# COM-TC.net
KiCad netlist of a schematic drawn in EAGLE
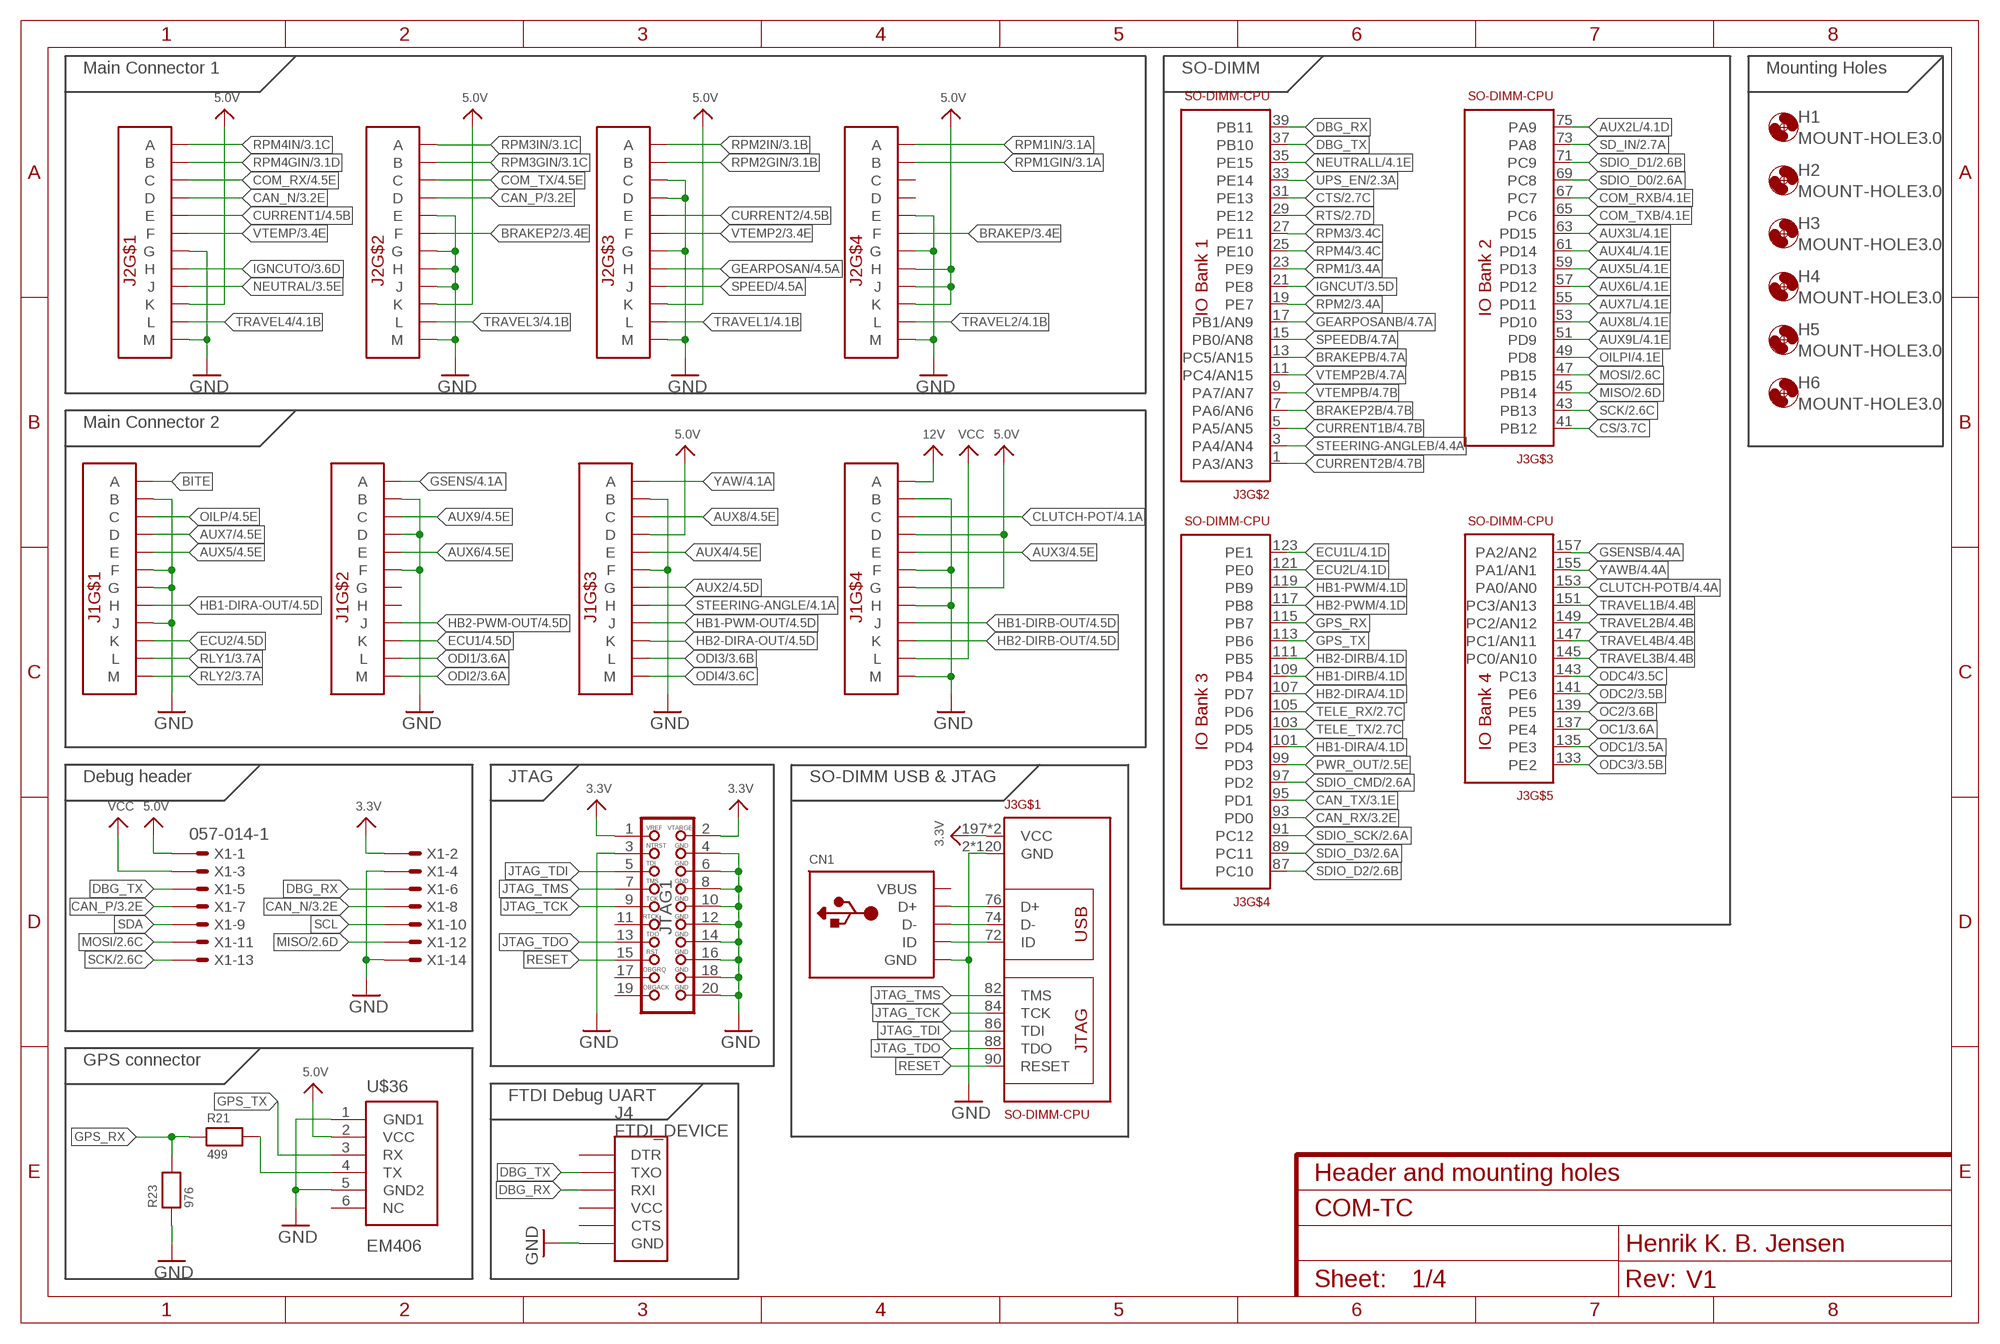
[diagram p0: schematic, sheet 1]
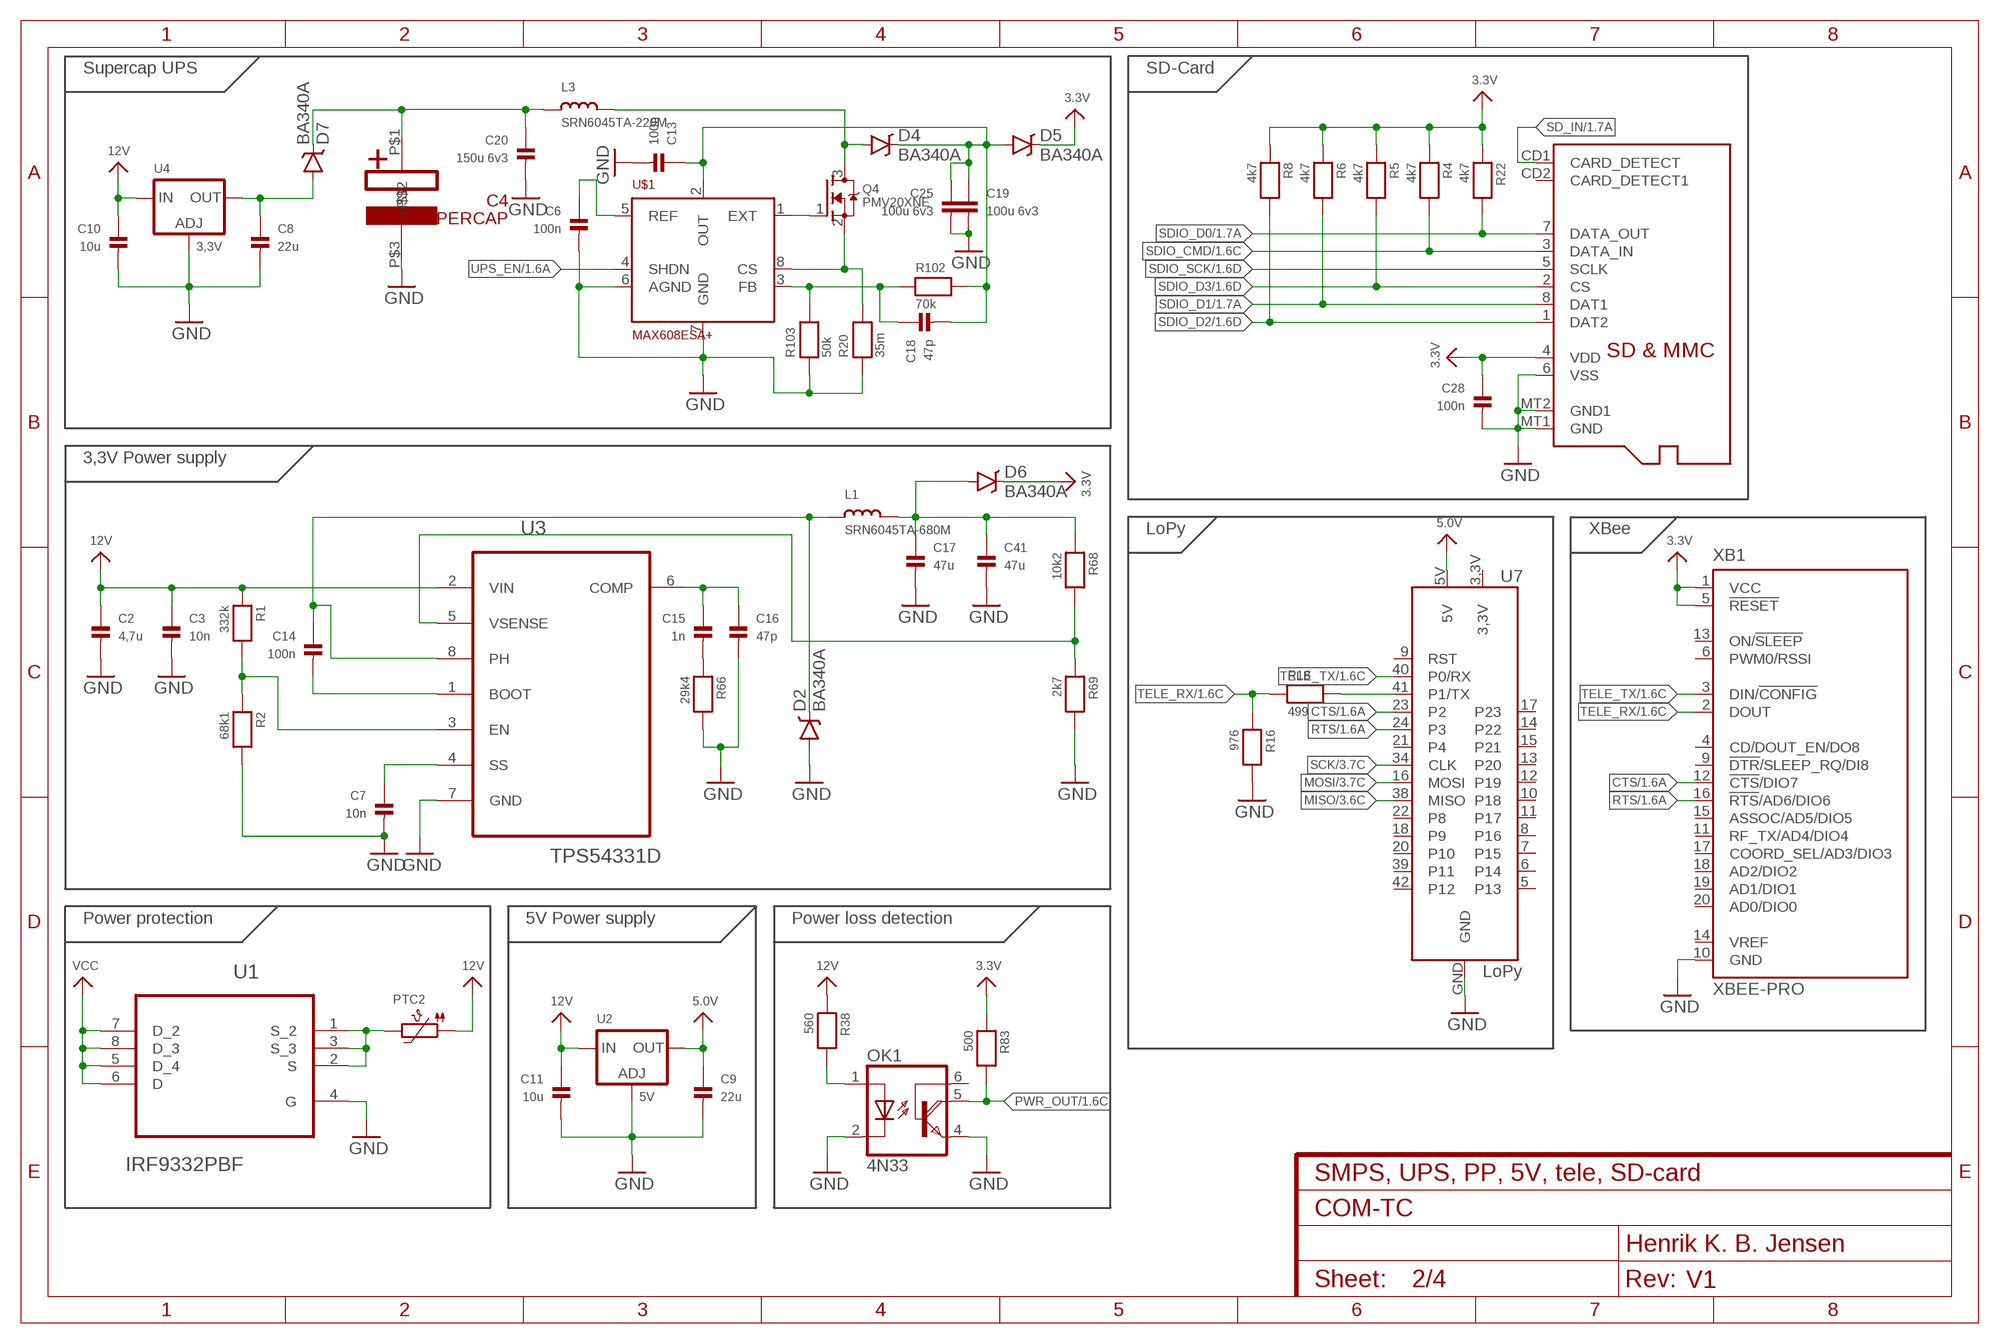
[diagram p1: schematic, sheet 2]
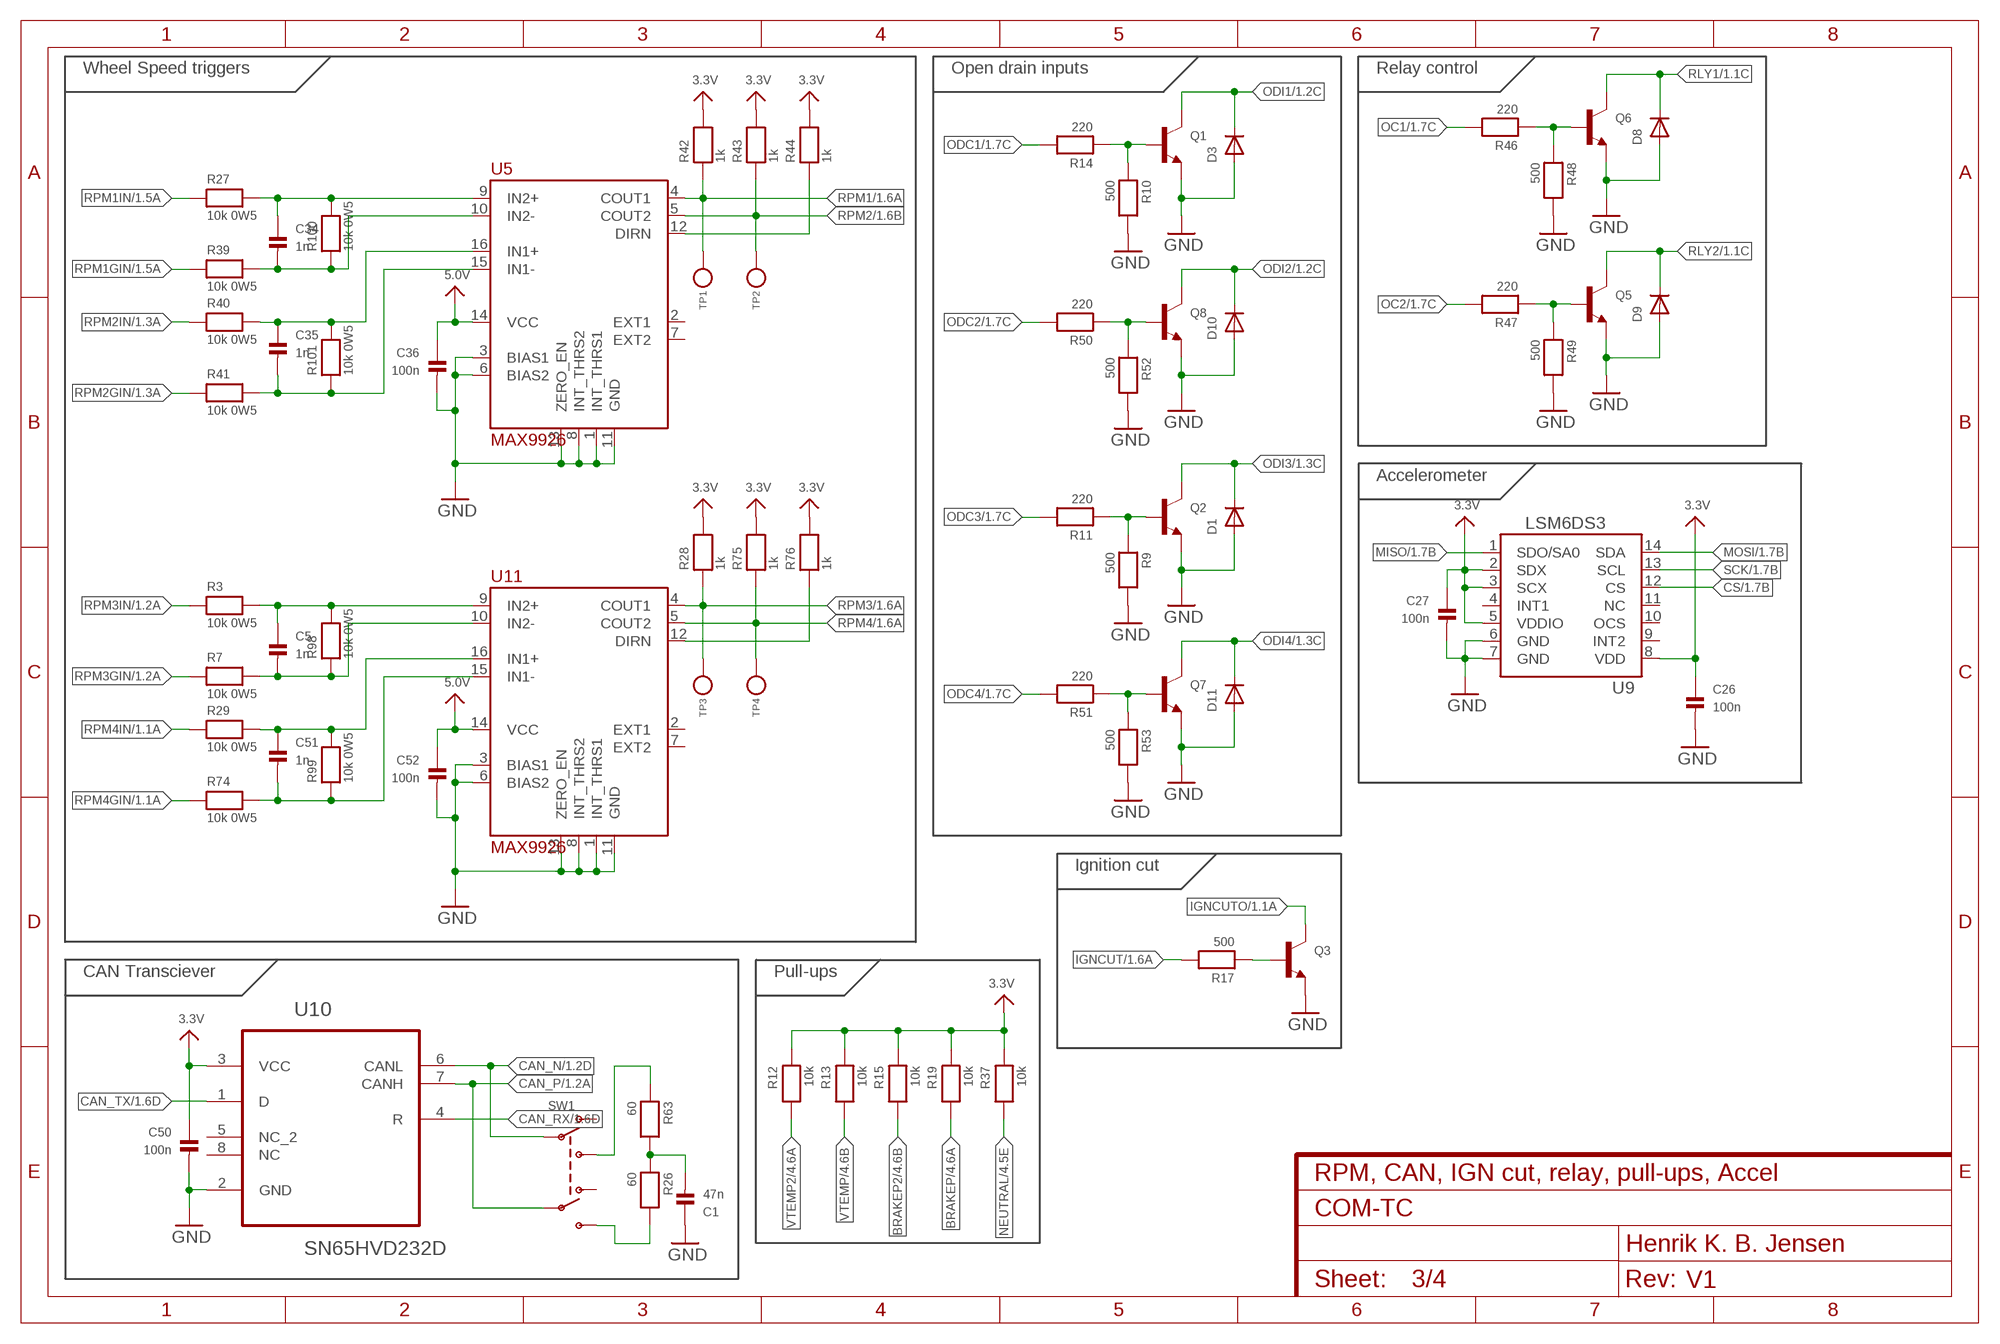
[diagram p2: schematic, sheet 3]
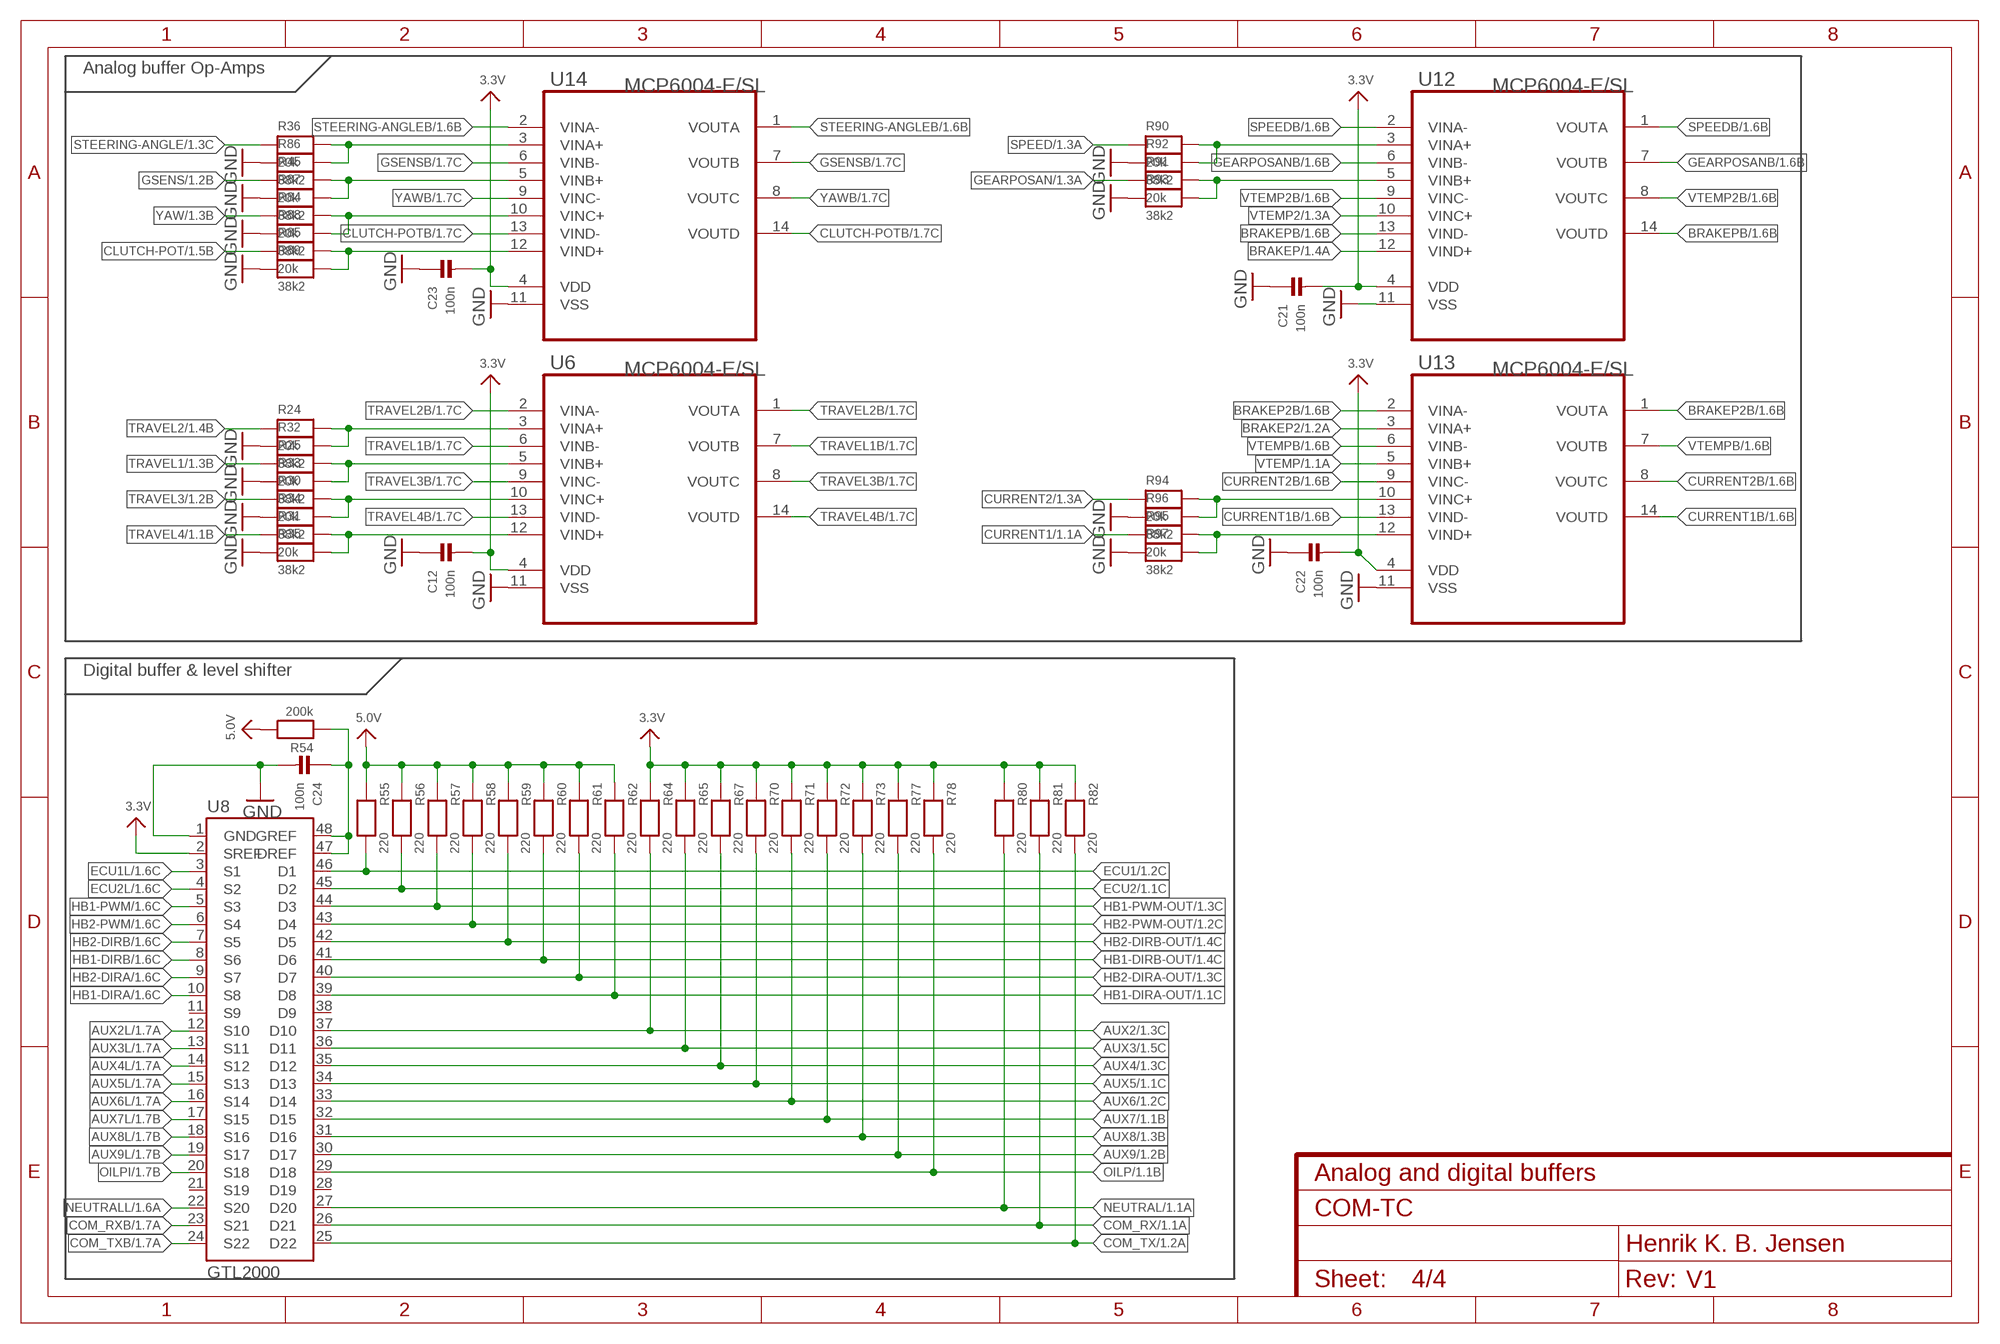
[diagram p3: schematic, sheet 4]

(export (version "E")
  (design (tool "Eeschema 10.0.6"))
  (components
    (comp (ref "C2")
      (value "4,7u")
      (footprint "eagle-import:_0805")
      (libsource (lib "eagle-import") (part "CAP_CERAMIC_0805"))
    )
    (comp (ref "C3")
      (value "10n")
      (footprint "eagle-import:_0603")
      (libsource (lib "eagle-import") (part "CAP_CERAMIC_0603"))
    )
    (comp (ref "C4")
      (value "SUPERCAP")
      (footprint "eagle-import:SUPERCAP")
      (libsource (lib "eagle-import") (part "SUPERCAP"))
    )
    (comp (ref "C6")
      (value "100n")
      (footprint "eagle-import:_0603")
      (libsource (lib "eagle-import") (part "CAP_CERAMIC_0603"))
    )
    (comp (ref "C7")
      (value "10n")
      (footprint "eagle-import:_0603")
      (libsource (lib "eagle-import") (part "CAP_CERAMIC_0603"))
    )
    (comp (ref "C8")
      (value "22u")
      (footprint "eagle-import:_0805")
      (libsource (lib "eagle-import") (part "CAP_CERAMIC_0805"))
    )
    (comp (ref "C9")
      (value "22u")
      (footprint "eagle-import:_0805")
      (libsource (lib "eagle-import") (part "CAP_CERAMIC_0805"))
    )
    (comp (ref "C10")
      (value "10u")
      (footprint "eagle-import:_0805")
      (libsource (lib "eagle-import") (part "CAP_CERAMIC_0805"))
    )
    (comp (ref "C11")
      (value "10u")
      (footprint "eagle-import:_0805")
      (libsource (lib "eagle-import") (part "CAP_CERAMIC_0805"))
    )
    (comp (ref "C13")
      (value "100n")
      (footprint "eagle-import:_0603")
      (libsource (lib "eagle-import") (part "CAP_CERAMIC_0603"))
    )
    (comp (ref "C14")
      (value "100n")
      (footprint "eagle-import:_0603")
      (libsource (lib "eagle-import") (part "CAP_CERAMIC_0603"))
    )
    (comp (ref "C15")
      (value "1n")
      (footprint "eagle-import:_0603")
      (libsource (lib "eagle-import") (part "CAP_CERAMIC_0603"))
    )
    (comp (ref "C16")
      (value "47p")
      (footprint "eagle-import:_0603")
      (libsource (lib "eagle-import") (part "CAP_CERAMIC_0603"))
    )
    (comp (ref "C17")
      (value "47u")
      (footprint "eagle-import:_0805")
      (libsource (lib "eagle-import") (part "CAP_CERAMIC_0805"))
    )
    (comp (ref "C18")
      (value "47p")
      (footprint "eagle-import:_0603")
      (libsource (lib "eagle-import") (part "CAP_CERAMIC_0603"))
    )
    (comp (ref "C19")
      (value "100u 6v3")
      (footprint "eagle-import:1206")
      (libsource (lib "eagle-import") (part "CAP_CERAMIC1206"))
    )
    (comp (ref "C20")
      (value "150u 6v3")
      (footprint "eagle-import:1206")
      (libsource (lib "eagle-import") (part "CAP_CERAMIC1206"))
    )
    (comp (ref "C25")
      (value "100u 6v3")
      (footprint "eagle-import:1206")
      (libsource (lib "eagle-import") (part "CAP_CERAMIC1206"))
    )
    (comp (ref "C28")
      (value "100n")
      (footprint "eagle-import:_0603")
      (libsource (lib "eagle-import") (part "CAP_CERAMIC_0603"))
    )
    (comp (ref "C41")
      (value "47u")
      (footprint "eagle-import:_0805")
      (libsource (lib "eagle-import") (part "CAP_CERAMIC_0805"))
    )
    (comp (ref "D2")
      (value "BA340A")
      (footprint "eagle-import:SMA-DIODE")
      (libsource (lib "eagle-import") (part "B340A"))
    )
    (comp (ref "D4")
      (value "BA340A")
      (footprint "eagle-import:SMA-DIODE")
      (libsource (lib "eagle-import") (part "B340A"))
    )
    (comp (ref "D5")
      (value "BA340A")
      (footprint "eagle-import:SMA-DIODE")
      (libsource (lib "eagle-import") (part "B340A"))
    )
    (comp (ref "D6")
      (value "BA340A")
      (footprint "eagle-import:SMA-DIODE")
      (libsource (lib "eagle-import") (part "B340A"))
    )
    (comp (ref "D7")
      (value "BA340A")
      (footprint "eagle-import:SMA-DIODE")
      (libsource (lib "eagle-import") (part "B340A"))
    )
    (comp (ref "L1")
      (value "SRN6045TA-680M")
      (footprint "eagle-import:INDUCTOR_6X6MM_TDK_VLC6045")
      (libsource (lib "eagle-import") (part "INDUCTORTDK_VLC6045"))
    )
    (comp (ref "L3")
      (value "SRN6045TA-220M")
      (footprint "eagle-import:INDUCTOR_6X6MM_TDK_VLC6045")
      (libsource (lib "eagle-import") (part "INDUCTORTDK_VLC6045"))
    )
    (comp (ref "OK1")
      (value "4N33")
      (footprint "eagle-import:DIL06")
      (fields (field (name "MF") "VISHAY/TELEFUNKEN"))
      (libsource (lib "eagle-import") (part "4N33"))
    )
    (comp (ref "PTC2")
      (value "PTC1812")
      (footprint "eagle-import:PTC1812")
      (libsource (lib "eagle-import") (part "PTC1812"))
    )
    (comp (ref "Q4")
      (value "PMV20XNE")
      (footprint "eagle-import:SOT23")
      (libsource (lib "eagle-import") (part "MOSFET-NREFLOW"))
    )
    (comp (ref "R1")
      (value "332k")
      (footprint "eagle-import:_0603")
      (libsource (lib "eagle-import") (part "RESISTOR_0603"))
    )
    (comp (ref "R2")
      (value "68k1")
      (footprint "eagle-import:_0603")
      (libsource (lib "eagle-import") (part "RESISTOR_0603"))
    )
    (comp (ref "R4")
      (value "4k7")
      (footprint "eagle-import:_0603")
      (libsource (lib "eagle-import") (part "RESISTOR_0603"))
    )
    (comp (ref "R5")
      (value "4k7")
      (footprint "eagle-import:_0603")
      (libsource (lib "eagle-import") (part "RESISTOR_0603"))
    )
    (comp (ref "R6")
      (value "4k7")
      (footprint "eagle-import:_0603")
      (libsource (lib "eagle-import") (part "RESISTOR_0603"))
    )
    (comp (ref "R8")
      (value "4k7")
      (footprint "eagle-import:_0603")
      (libsource (lib "eagle-import") (part "RESISTOR_0603"))
    )
    (comp (ref "R16")
      (value "976")
      (footprint "eagle-import:_0603")
      (libsource (lib "eagle-import") (part "RESISTOR_0603"))
    )
    (comp (ref "R18")
      (value "499")
      (footprint "eagle-import:_0603")
      (libsource (lib "eagle-import") (part "RESISTOR_0603"))
    )
    (comp (ref "R20")
      (value "35m")
      (footprint "eagle-import:1206")
      (libsource (lib "eagle-import") (part "RESISTOR1206"))
    )
    (comp (ref "R22")
      (value "4k7")
      (footprint "eagle-import:_0603")
      (libsource (lib "eagle-import") (part "RESISTOR_0603"))
    )
    (comp (ref "R38")
      (value "560")
      (footprint "eagle-import:_0603")
      (libsource (lib "eagle-import") (part "RESISTOR_0603"))
    )
    (comp (ref "R66")
      (value "29k4")
      (footprint "eagle-import:_0603")
      (libsource (lib "eagle-import") (part "RESISTOR_0603"))
    )
    (comp (ref "R68")
      (value "10k2")
      (footprint "eagle-import:_0603")
      (libsource (lib "eagle-import") (part "RESISTOR_0603"))
    )
    (comp (ref "R69")
      (value "2k7")
      (footprint "eagle-import:_0603")
      (libsource (lib "eagle-import") (part "RESISTOR_0603"))
    )
    (comp (ref "R83")
      (value "500")
      (footprint "eagle-import:_0603")
      (libsource (lib "eagle-import") (part "RESISTOR_0603"))
    )
    (comp (ref "R102")
      (value "70k")
      (footprint "eagle-import:_0603")
      (libsource (lib "eagle-import") (part "RESISTOR_0603"))
    )
    (comp (ref "R103")
      (value "50k")
      (footprint "eagle-import:_0603")
      (libsource (lib "eagle-import") (part "RESISTOR_0603"))
    )
    (comp (ref "U$1")
      (value "MAX608ESA+")
      (footprint "eagle-import:SO08")
      (libsource (lib "eagle-import") (part "MAX608ESA+"))
    )
    (comp (ref "U$2")
      (value "MICROSD")
      (footprint "eagle-import:MICROSD")
      (libsource (lib "eagle-import") (part "MICROSD"))
    )
    (comp (ref "U1")
      (value "IRF9332PBF")
      (footprint "eagle-import:SOIC127P600X175-8N")
      (libsource (lib "eagle-import") (part "IRF9332PBF"))
    )
    (comp (ref "U2")
      (value "5V")
      (footprint "eagle-import:SOT223-R")
      (libsource (lib "eagle-import") (part "LM1117SOT223-REFLOW"))
    )
    (comp (ref "U3")
      (value "TPS54331D")
      (footprint "eagle-import:SOIC127P600X175-8N")
      (libsource (lib "eagle-import") (part "TPS54331D"))
    )
    (comp (ref "U4")
      (value "3,3V")
      (footprint "eagle-import:SOT223-R")
      (libsource (lib "eagle-import") (part "LM1117SOT223-REFLOW"))
    )
    (comp (ref "U7")
      (value "LoPy")
      (footprint "eagle-import:LOPY")
      (libsource (lib "eagle-import") (part "LOPY"))
    )
    (comp (ref "XB1")
      (value "XBEE-PRO")
      (footprint "eagle-import:XBEE-PRO")
      (fields (field (name "MPN") "XBP24-AWI-001"))
      (libsource (lib "eagle-import") (part "XBEE-PRO"))
    )
    (comp (ref "C1")
      (value "47n")
      (footprint "eagle-import:_0603")
      (libsource (lib "eagle-import") (part "CAP_CERAMIC_0603"))
    )
    (comp (ref "C5")
      (value "1n")
      (footprint "eagle-import:_0603")
      (libsource (lib "eagle-import") (part "CAP_CERAMIC_0603"))
    )
    (comp (ref "C26")
      (value "100n")
      (footprint "eagle-import:_0603")
      (libsource (lib "eagle-import") (part "CAP_CERAMIC_0603"))
    )
    (comp (ref "C27")
      (value "100n")
      (footprint "eagle-import:_0603")
      (libsource (lib "eagle-import") (part "CAP_CERAMIC_0603"))
    )
    (comp (ref "C34")
      (value "1n")
      (footprint "eagle-import:_0603")
      (libsource (lib "eagle-import") (part "CAP_CERAMIC_0603"))
    )
    (comp (ref "C35")
      (value "1n")
      (footprint "eagle-import:_0603")
      (libsource (lib "eagle-import") (part "CAP_CERAMIC_0603"))
    )
    (comp (ref "C36")
      (value "100n")
      (footprint "eagle-import:_0603")
      (libsource (lib "eagle-import") (part "CAP_CERAMIC_0603"))
    )
    (comp (ref "C50")
      (value "100n")
      (footprint "eagle-import:_0603")
      (libsource (lib "eagle-import") (part "CAP_CERAMIC_0603"))
    )
    (comp (ref "C51")
      (value "1n")
      (footprint "eagle-import:_0603")
      (libsource (lib "eagle-import") (part "CAP_CERAMIC_0603"))
    )
    (comp (ref "C52")
      (value "100n")
      (footprint "eagle-import:_0603")
      (libsource (lib "eagle-import") (part "CAP_CERAMIC_0603"))
    )
    (comp (ref "D1")
      (value "DIODESOD-323F")
      (footprint "eagle-import:SOD-323F")
      (libsource (lib "eagle-import") (part "DIODESOD-323F"))
    )
    (comp (ref "D3")
      (value "DIODESOD-323F")
      (footprint "eagle-import:SOD-323F")
      (libsource (lib "eagle-import") (part "DIODESOD-323F"))
    )
    (comp (ref "D8")
      (value "DIODESOD-323F")
      (footprint "eagle-import:SOD-323F")
      (libsource (lib "eagle-import") (part "DIODESOD-323F"))
    )
    (comp (ref "D9")
      (value "DIODESOD-323F")
      (footprint "eagle-import:SOD-323F")
      (libsource (lib "eagle-import") (part "DIODESOD-323F"))
    )
    (comp (ref "D10")
      (value "DIODESOD-323F")
      (footprint "eagle-import:SOD-323F")
      (libsource (lib "eagle-import") (part "DIODESOD-323F"))
    )
    (comp (ref "D11")
      (value "DIODESOD-323F")
      (footprint "eagle-import:SOD-323F")
      (libsource (lib "eagle-import") (part "DIODESOD-323F"))
    )
    (comp (ref "Q1")
      (value "TRANSISTOR_NPNWIDE")
      (footprint "eagle-import:SOT23-WIDE")
      (libsource (lib "eagle-import") (part "TRANSISTOR_NPNWIDE"))
    )
    (comp (ref "Q2")
      (value "TRANSISTOR_NPNWIDE")
      (footprint "eagle-import:SOT23-WIDE")
      (libsource (lib "eagle-import") (part "TRANSISTOR_NPNWIDE"))
    )
    (comp (ref "Q3")
      (value "TRANSISTOR_NPNWIDE")
      (footprint "eagle-import:SOT23-WIDE")
      (libsource (lib "eagle-import") (part "TRANSISTOR_NPNWIDE"))
    )
    (comp (ref "Q5")
      (value "TRANSISTOR_NPNWIDE")
      (footprint "eagle-import:SOT23-WIDE")
      (libsource (lib "eagle-import") (part "TRANSISTOR_NPNWIDE"))
    )
    (comp (ref "Q6")
      (value "TRANSISTOR_NPNWIDE")
      (footprint "eagle-import:SOT23-WIDE")
      (libsource (lib "eagle-import") (part "TRANSISTOR_NPNWIDE"))
    )
    (comp (ref "Q7")
      (value "TRANSISTOR_NPNWIDE")
      (footprint "eagle-import:SOT23-WIDE")
      (libsource (lib "eagle-import") (part "TRANSISTOR_NPNWIDE"))
    )
    (comp (ref "Q8")
      (value "TRANSISTOR_NPNWIDE")
      (footprint "eagle-import:SOT23-WIDE")
      (libsource (lib "eagle-import") (part "TRANSISTOR_NPNWIDE"))
    )
    (comp (ref "R3")
      (value "10k 0W5")
      (footprint "eagle-import:_0805")
      (libsource (lib "eagle-import") (part "RESISTOR_0805"))
    )
    (comp (ref "R7")
      (value "10k 0W5")
      (footprint "eagle-import:_0805")
      (libsource (lib "eagle-import") (part "RESISTOR_0805"))
    )
    (comp (ref "R9")
      (value "500")
      (footprint "eagle-import:_0603")
      (libsource (lib "eagle-import") (part "RESISTOR_0603"))
    )
    (comp (ref "R10")
      (value "500")
      (footprint "eagle-import:_0603")
      (libsource (lib "eagle-import") (part "RESISTOR_0603"))
    )
    (comp (ref "R11")
      (value "220")
      (footprint "eagle-import:_0603")
      (libsource (lib "eagle-import") (part "RESISTOR_0603"))
    )
    (comp (ref "R12")
      (value "10k")
      (footprint "eagle-import:_0603")
      (libsource (lib "eagle-import") (part "RESISTOR_0603"))
    )
    (comp (ref "R13")
      (value "10k")
      (footprint "eagle-import:_0603")
      (libsource (lib "eagle-import") (part "RESISTOR_0603"))
    )
    (comp (ref "R14")
      (value "220")
      (footprint "eagle-import:_0603")
      (libsource (lib "eagle-import") (part "RESISTOR_0603"))
    )
    (comp (ref "R15")
      (value "10k")
      (footprint "eagle-import:_0603")
      (libsource (lib "eagle-import") (part "RESISTOR_0603"))
    )
    (comp (ref "R17")
      (value "500")
      (footprint "eagle-import:_0603")
      (libsource (lib "eagle-import") (part "RESISTOR_0603"))
    )
    (comp (ref "R19")
      (value "10k")
      (footprint "eagle-import:_0603")
      (libsource (lib "eagle-import") (part "RESISTOR_0603"))
    )
    (comp (ref "R26")
      (value "60")
      (footprint "eagle-import:_0603")
      (libsource (lib "eagle-import") (part "RESISTOR_0603"))
    )
    (comp (ref "R27")
      (value "10k 0W5")
      (footprint "eagle-import:_0805")
      (libsource (lib "eagle-import") (part "RESISTOR_0805"))
    )
    (comp (ref "R28")
      (value "1k")
      (footprint "eagle-import:_0603")
      (libsource (lib "eagle-import") (part "RESISTOR_0603"))
    )
    (comp (ref "R29")
      (value "10k 0W5")
      (footprint "eagle-import:_0805")
      (libsource (lib "eagle-import") (part "RESISTOR_0805"))
    )
    (comp (ref "R37")
      (value "10k")
      (footprint "eagle-import:_0603")
      (libsource (lib "eagle-import") (part "RESISTOR_0603"))
    )
    (comp (ref "R39")
      (value "10k 0W5")
      (footprint "eagle-import:_0805")
      (libsource (lib "eagle-import") (part "RESISTOR_0805"))
    )
    (comp (ref "R40")
      (value "10k 0W5")
      (footprint "eagle-import:_0805")
      (libsource (lib "eagle-import") (part "RESISTOR_0805"))
    )
    (comp (ref "R41")
      (value "10k 0W5")
      (footprint "eagle-import:_0805")
      (libsource (lib "eagle-import") (part "RESISTOR_0805"))
    )
    (comp (ref "R42")
      (value "1k")
      (footprint "eagle-import:_0603")
      (libsource (lib "eagle-import") (part "RESISTOR_0603"))
    )
    (comp (ref "R43")
      (value "1k")
      (footprint "eagle-import:_0603")
      (libsource (lib "eagle-import") (part "RESISTOR_0603"))
    )
    (comp (ref "R44")
      (value "1k")
      (footprint "eagle-import:_0603")
      (libsource (lib "eagle-import") (part "RESISTOR_0603"))
    )
    (comp (ref "R46")
      (value "220")
      (footprint "eagle-import:_0603")
      (libsource (lib "eagle-import") (part "RESISTOR_0603"))
    )
    (comp (ref "R47")
      (value "220")
      (footprint "eagle-import:_0603")
      (libsource (lib "eagle-import") (part "RESISTOR_0603"))
    )
    (comp (ref "R48")
      (value "500")
      (footprint "eagle-import:_0603")
      (libsource (lib "eagle-import") (part "RESISTOR_0603"))
    )
    (comp (ref "R49")
      (value "500")
      (footprint "eagle-import:_0603")
      (libsource (lib "eagle-import") (part "RESISTOR_0603"))
    )
    (comp (ref "R50")
      (value "220")
      (footprint "eagle-import:_0603")
      (libsource (lib "eagle-import") (part "RESISTOR_0603"))
    )
    (comp (ref "R51")
      (value "220")
      (footprint "eagle-import:_0603")
      (libsource (lib "eagle-import") (part "RESISTOR_0603"))
    )
    (comp (ref "R52")
      (value "500")
      (footprint "eagle-import:_0603")
      (libsource (lib "eagle-import") (part "RESISTOR_0603"))
    )
    (comp (ref "R53")
      (value "500")
      (footprint "eagle-import:_0603")
      (libsource (lib "eagle-import") (part "RESISTOR_0603"))
    )
    (comp (ref "R63")
      (value "60")
      (footprint "eagle-import:_0603")
      (libsource (lib "eagle-import") (part "RESISTOR_0603"))
    )
    (comp (ref "R74")
      (value "10k 0W5")
      (footprint "eagle-import:_0805")
      (libsource (lib "eagle-import") (part "RESISTOR_0805"))
    )
    (comp (ref "R75")
      (value "1k")
      (footprint "eagle-import:_0603")
      (libsource (lib "eagle-import") (part "RESISTOR_0603"))
    )
    (comp (ref "R76")
      (value "1k")
      (footprint "eagle-import:_0603")
      (libsource (lib "eagle-import") (part "RESISTOR_0603"))
    )
    (comp (ref "R98")
      (value "10k 0W5")
      (footprint "eagle-import:_0805")
      (libsource (lib "eagle-import") (part "RESISTOR_0805"))
    )
    (comp (ref "R99")
      (value "10k 0W5")
      (footprint "eagle-import:_0805")
      (libsource (lib "eagle-import") (part "RESISTOR_0805"))
    )
    (comp (ref "R100")
      (value "10k 0W5")
      (footprint "eagle-import:_0805")
      (libsource (lib "eagle-import") (part "RESISTOR_0805"))
    )
    (comp (ref "R101")
      (value "10k 0W5")
      (footprint "eagle-import:_0805")
      (libsource (lib "eagle-import") (part "RESISTOR_0805"))
    )
    (comp (ref "SW1")
      (value "SWITCH_DPDT")
      (footprint "eagle-import:DPDT_SMT_JS202011SCQN")
      (libsource (lib "eagle-import") (part "SWITCH_DPDT"))
    )
    (comp (ref "TP1")
      (value "TEST_POINT_0.040IN")
      (footprint "eagle-import:TESTPOINT_0.040IN")
      (libsource (lib "eagle-import") (part "TEST_POINT_0.040IN"))
    )
    (comp (ref "TP2")
      (value "TEST_POINT_0.040IN")
      (footprint "eagle-import:TESTPOINT_0.040IN")
      (libsource (lib "eagle-import") (part "TEST_POINT_0.040IN"))
    )
    (comp (ref "TP3")
      (value "TEST_POINT_0.040IN")
      (footprint "eagle-import:TESTPOINT_0.040IN")
      (libsource (lib "eagle-import") (part "TEST_POINT_0.040IN"))
    )
    (comp (ref "TP4")
      (value "TEST_POINT_0.040IN")
      (footprint "eagle-import:TESTPOINT_0.040IN")
      (libsource (lib "eagle-import") (part "TEST_POINT_0.040IN"))
    )
    (comp (ref "U5")
      (value "MAX9926")
      (footprint "eagle-import:SOP63P600X175-16N")
      (libsource (lib "eagle-import") (part "MAX9926"))
    )
    (comp (ref "U9")
      (value "LSM6DS3")
      (footprint "eagle-import:LGA14L_DOT_INDICATOR")
      (libsource (lib "eagle-import") (part "LSM6DS3DOT_INDICATION"))
    )
    (comp (ref "U10")
      (value "SN65HVD232D")
      (footprint "eagle-import:SOIC127P600X175-8N")
      (libsource (lib "eagle-import") (part "SN65HVD232D"))
    )
    (comp (ref "U11")
      (value "MAX9926")
      (footprint "eagle-import:SOP63P600X175-16N")
      (libsource (lib "eagle-import") (part "MAX9926"))
    )
    (comp (ref "C12")
      (value "100n")
      (footprint "eagle-import:_0603")
      (libsource (lib "eagle-import") (part "CAP_CERAMIC_0603"))
    )
    (comp (ref "C21")
      (value "100n")
      (footprint "eagle-import:_0603")
      (libsource (lib "eagle-import") (part "CAP_CERAMIC_0603"))
    )
    (comp (ref "C22")
      (value "100n")
      (footprint "eagle-import:_0603")
      (libsource (lib "eagle-import") (part "CAP_CERAMIC_0603"))
    )
    (comp (ref "C23")
      (value "100n")
      (footprint "eagle-import:_0603")
      (libsource (lib "eagle-import") (part "CAP_CERAMIC_0603"))
    )
    (comp (ref "C24")
      (value "100n")
      (footprint "eagle-import:_0603")
      (libsource (lib "eagle-import") (part "CAP_CERAMIC_0603"))
    )
    (comp (ref "R24")
      (value "20k")
      (footprint "eagle-import:_0603")
      (libsource (lib "eagle-import") (part "RESISTOR_0603"))
    )
    (comp (ref "R25")
      (value "20k")
      (footprint "eagle-import:_0603")
      (libsource (lib "eagle-import") (part "RESISTOR_0603"))
    )
    (comp (ref "R30")
      (value "20k")
      (footprint "eagle-import:_0603")
      (libsource (lib "eagle-import") (part "RESISTOR_0603"))
    )
    (comp (ref "R31")
      (value "20k")
      (footprint "eagle-import:_0603")
      (libsource (lib "eagle-import") (part "RESISTOR_0603"))
    )
    (comp (ref "R32")
      (value "38k2")
      (footprint "eagle-import:_0603")
      (libsource (lib "eagle-import") (part "RESISTOR_0603"))
    )
    (comp (ref "R33")
      (value "38k2")
      (footprint "eagle-import:_0603")
      (libsource (lib "eagle-import") (part "RESISTOR_0603"))
    )
    (comp (ref "R34")
      (value "38k2")
      (footprint "eagle-import:_0603")
      (libsource (lib "eagle-import") (part "RESISTOR_0603"))
    )
    (comp (ref "R35")
      (value "38k2")
      (footprint "eagle-import:_0603")
      (libsource (lib "eagle-import") (part "RESISTOR_0603"))
    )
    (comp (ref "R36")
      (value "20k")
      (footprint "eagle-import:_0603")
      (libsource (lib "eagle-import") (part "RESISTOR_0603"))
    )
    (comp (ref "R45")
      (value "20k")
      (footprint "eagle-import:_0603")
      (libsource (lib "eagle-import") (part "RESISTOR_0603"))
    )
    (comp (ref "R54")
      (value "200k")
      (footprint "eagle-import:_0603")
      (libsource (lib "eagle-import") (part "RESISTOR_0603"))
    )
    (comp (ref "R55")
      (value "220")
      (footprint "eagle-import:_0603")
      (libsource (lib "eagle-import") (part "RESISTOR_0603"))
    )
    (comp (ref "R56")
      (value "220")
      (footprint "eagle-import:_0603")
      (libsource (lib "eagle-import") (part "RESISTOR_0603"))
    )
    (comp (ref "R57")
      (value "220")
      (footprint "eagle-import:_0603")
      (libsource (lib "eagle-import") (part "RESISTOR_0603"))
    )
    (comp (ref "R58")
      (value "220")
      (footprint "eagle-import:_0603")
      (libsource (lib "eagle-import") (part "RESISTOR_0603"))
    )
    (comp (ref "R59")
      (value "220")
      (footprint "eagle-import:_0603")
      (libsource (lib "eagle-import") (part "RESISTOR_0603"))
    )
    (comp (ref "R60")
      (value "220")
      (footprint "eagle-import:_0603")
      (libsource (lib "eagle-import") (part "RESISTOR_0603"))
    )
    (comp (ref "R61")
      (value "220")
      (footprint "eagle-import:_0603")
      (libsource (lib "eagle-import") (part "RESISTOR_0603"))
    )
    (comp (ref "R62")
      (value "220")
      (footprint "eagle-import:_0603")
      (libsource (lib "eagle-import") (part "RESISTOR_0603"))
    )
    (comp (ref "R64")
      (value "220")
      (footprint "eagle-import:_0603")
      (libsource (lib "eagle-import") (part "RESISTOR_0603"))
    )
    (comp (ref "R65")
      (value "220")
      (footprint "eagle-import:_0603")
      (libsource (lib "eagle-import") (part "RESISTOR_0603"))
    )
    (comp (ref "R67")
      (value "220")
      (footprint "eagle-import:_0603")
      (libsource (lib "eagle-import") (part "RESISTOR_0603"))
    )
    (comp (ref "R70")
      (value "220")
      (footprint "eagle-import:_0603")
      (libsource (lib "eagle-import") (part "RESISTOR_0603"))
    )
    (comp (ref "R71")
      (value "220")
      (footprint "eagle-import:_0603")
      (libsource (lib "eagle-import") (part "RESISTOR_0603"))
    )
    (comp (ref "R72")
      (value "220")
      (footprint "eagle-import:_0603")
      (libsource (lib "eagle-import") (part "RESISTOR_0603"))
    )
    (comp (ref "R73")
      (value "220")
      (footprint "eagle-import:_0603")
      (libsource (lib "eagle-import") (part "RESISTOR_0603"))
    )
    (comp (ref "R77")
      (value "220")
      (footprint "eagle-import:_0603")
      (libsource (lib "eagle-import") (part "RESISTOR_0603"))
    )
    (comp (ref "R78")
      (value "220")
      (footprint "eagle-import:_0603")
      (libsource (lib "eagle-import") (part "RESISTOR_0603"))
    )
    (comp (ref "R80")
      (value "220")
      (footprint "eagle-import:_0603")
      (libsource (lib "eagle-import") (part "RESISTOR_0603"))
    )
    (comp (ref "R81")
      (value "220")
      (footprint "eagle-import:_0603")
      (libsource (lib "eagle-import") (part "RESISTOR_0603"))
    )
    (comp (ref "R82")
      (value "220")
      (footprint "eagle-import:_0603")
      (libsource (lib "eagle-import") (part "RESISTOR_0603"))
    )
    (comp (ref "R84")
      (value "20k")
      (footprint "eagle-import:_0603")
      (libsource (lib "eagle-import") (part "RESISTOR_0603"))
    )
    (comp (ref "R85")
      (value "20k")
      (footprint "eagle-import:_0603")
      (libsource (lib "eagle-import") (part "RESISTOR_0603"))
    )
    (comp (ref "R86")
      (value "38k2")
      (footprint "eagle-import:_0603")
      (libsource (lib "eagle-import") (part "RESISTOR_0603"))
    )
    (comp (ref "R87")
      (value "38k2")
      (footprint "eagle-import:_0603")
      (libsource (lib "eagle-import") (part "RESISTOR_0603"))
    )
    (comp (ref "R88")
      (value "38k2")
      (footprint "eagle-import:_0603")
      (libsource (lib "eagle-import") (part "RESISTOR_0603"))
    )
    (comp (ref "R89")
      (value "38k2")
      (footprint "eagle-import:_0603")
      (libsource (lib "eagle-import") (part "RESISTOR_0603"))
    )
    (comp (ref "R90")
      (value "20k")
      (footprint "eagle-import:_0603")
      (libsource (lib "eagle-import") (part "RESISTOR_0603"))
    )
    (comp (ref "R91")
      (value "20k")
      (footprint "eagle-import:_0603")
      (libsource (lib "eagle-import") (part "RESISTOR_0603"))
    )
    (comp (ref "R92")
      (value "38k2")
      (footprint "eagle-import:_0603")
      (libsource (lib "eagle-import") (part "RESISTOR_0603"))
    )
    (comp (ref "R93")
      (value "38k2")
      (footprint "eagle-import:_0603")
      (libsource (lib "eagle-import") (part "RESISTOR_0603"))
    )
    (comp (ref "R94")
      (value "20k")
      (footprint "eagle-import:_0603")
      (libsource (lib "eagle-import") (part "RESISTOR_0603"))
    )
    (comp (ref "R95")
      (value "20k")
      (footprint "eagle-import:_0603")
      (libsource (lib "eagle-import") (part "RESISTOR_0603"))
    )
    (comp (ref "R96")
      (value "38k2")
      (footprint "eagle-import:_0603")
      (libsource (lib "eagle-import") (part "RESISTOR_0603"))
    )
    (comp (ref "R97")
      (value "38k2")
      (footprint "eagle-import:_0603")
      (libsource (lib "eagle-import") (part "RESISTOR_0603"))
    )
    (comp (ref "U6")
      (value "MCP6004-E/SL")
      (footprint "eagle-import:SOIC127P600X175-14N")
      (libsource (lib "eagle-import") (part "MCP6004-E/SL"))
    )
    (comp (ref "U8")
      (value "GTL2000")
      (footprint "eagle-import:TSSOP48")
      (libsource (lib "eagle-import") (part "GTL2000"))
    )
    (comp (ref "U12")
      (value "MCP6004-E/SL")
      (footprint "eagle-import:SOIC127P600X175-14N")
      (libsource (lib "eagle-import") (part "MCP6004-E/SL"))
    )
    (comp (ref "U13")
      (value "MCP6004-E/SL")
      (footprint "eagle-import:SOIC127P600X175-14N")
      (libsource (lib "eagle-import") (part "MCP6004-E/SL"))
    )
    (comp (ref "U14")
      (value "MCP6004-E/SL")
      (footprint "eagle-import:SOIC127P600X175-14N")
      (libsource (lib "eagle-import") (part "MCP6004-E/SL"))
    )
    (comp (ref "CN1")
      (value "USBMINIBLARGE")
      (footprint "eagle-import:USB-MINIB_LARGER")
      (libsource (lib "eagle-import") (part "USBMINIBLARGE"))
    )
    (comp (ref "H1")
      (value "MOUNT-HOLE3.0")
      (footprint "eagle-import:3,0")
      (libsource (lib "eagle-import") (part "MOUNT-HOLE3.0"))
    )
    (comp (ref "H2")
      (value "MOUNT-HOLE3.0")
      (footprint "eagle-import:3,0")
      (libsource (lib "eagle-import") (part "MOUNT-HOLE3.0"))
    )
    (comp (ref "H3")
      (value "MOUNT-HOLE3.0")
      (footprint "eagle-import:3,0")
      (libsource (lib "eagle-import") (part "MOUNT-HOLE3.0"))
    )
    (comp (ref "H4")
      (value "MOUNT-HOLE3.0")
      (footprint "eagle-import:3,0")
      (libsource (lib "eagle-import") (part "MOUNT-HOLE3.0"))
    )
    (comp (ref "H5")
      (value "MOUNT-HOLE3.0")
      (footprint "eagle-import:3,0")
      (libsource (lib "eagle-import") (part "MOUNT-HOLE3.0"))
    )
    (comp (ref "H6")
      (value "MOUNT-HOLE3.0")
      (footprint "eagle-import:3,0")
      (libsource (lib "eagle-import") (part "MOUNT-HOLE3.0"))
    )
    (comp (ref "J1")
      (value "CON1")
      (footprint "eagle-import:AUTOCONNECTOR")
      (libsource (lib "eagle-import") (part "AUTOCONNECTOR"))
    )
    (comp (ref "J2")
      (value "CON1")
      (footprint "eagle-import:AUTOCONNECTOR")
      (libsource (lib "eagle-import") (part "AUTOCONNECTOR"))
    )
    (comp (ref "J3")
      (value "SO-DIMM-CPU")
      (footprint "eagle-import:SODIMM-CONNECTOR-2.5V")
      (libsource (lib "eagle-import") (part "SO-DIMM-CPU"))
    )
    (comp (ref "J4")
      (value "FTDI_DEVICE")
      (footprint "eagle-import:FTDI_DEVICE_SIDE")
      (libsource (lib "eagle-import") (part "FTDI_DEVICE"))
    )
    (comp (ref "JTAG1")
      (value "JTAG-ARM")
      (footprint "eagle-import:JTAG-ARM")
      (libsource (lib "eagle-import") (part "JTAG-ARM"))
    )
    (comp (ref "R21")
      (value "499")
      (footprint "eagle-import:_0603")
      (libsource (lib "eagle-import") (part "RESISTOR_0603"))
    )
    (comp (ref "R23")
      (value "976")
      (footprint "eagle-import:_0603")
      (libsource (lib "eagle-import") (part "RESISTOR_0603"))
    )
    (comp (ref "U$36")
      (value "EM406")
      (footprint "eagle-import:EM406")
      (libsource (lib "eagle-import") (part "EM406"))
    )
    (comp (ref "X1")
      (value "057-014-1")
      (footprint "eagle-import:057-014-1")
      (libsource (lib "eagle-import") (part "057-014-1"))
    )
  )
  (nets
    (net (code "1") (name "3.3V") (class "Default")
      (node (ref "C12") (pin "2") (pinfunction "P$2_2") (pintype "passive"))
      (node (ref "C21") (pin "2") (pinfunction "P$2_2") (pintype "passive"))
      (node (ref "C22") (pin "2") (pinfunction "P$2_2") (pintype "passive"))
      (node (ref "C23") (pin "2") (pinfunction "P$2_2") (pintype "passive"))
      (node (ref "C26") (pin "1") (pinfunction "P$1_1") (pintype "passive"))
      (node (ref "C27") (pin "1") (pinfunction "P$1_1") (pintype "passive"))
      (node (ref "C28") (pin "1") (pinfunction "P$1_1") (pintype "passive"))
      (node (ref "C50") (pin "1") (pinfunction "P$1_1") (pintype "passive"))
      (node (ref "D5") (pin "C") (pinfunction "C_C") (pintype "passive"))
      (node (ref "D6") (pin "C") (pinfunction "C_C") (pintype "passive"))
      (node (ref "J3") (pin "197") (pinfunction "VCC_197") (pintype "bidirectional"))
      (node (ref "J3") (pin "199") (pinfunction "VCC_199") (pintype "bidirectional"))
      (node (ref "JTAG1") (pin "1") (pinfunction "1_1") (pintype "passive"))
      (node (ref "JTAG1") (pin "2") (pinfunction "2_2") (pintype "passive"))
      (node (ref "R12") (pin "1") (pinfunction "1_1") (pintype "passive"))
      (node (ref "R13") (pin "1") (pinfunction "1_1") (pintype "passive"))
      (node (ref "R15") (pin "1") (pinfunction "1_1") (pintype "passive"))
      (node (ref "R19") (pin "1") (pinfunction "1_1") (pintype "passive"))
      (node (ref "R22") (pin "1") (pinfunction "1_1") (pintype "passive"))
      (node (ref "R28") (pin "2") (pinfunction "2_2") (pintype "passive"))
      (node (ref "R37") (pin "1") (pinfunction "1_1") (pintype "passive"))
      (node (ref "R4") (pin "1") (pinfunction "1_1") (pintype "passive"))
      (node (ref "R42") (pin "2") (pinfunction "2_2") (pintype "passive"))
      (node (ref "R43") (pin "2") (pinfunction "2_2") (pintype "passive"))
      (node (ref "R44") (pin "2") (pinfunction "2_2") (pintype "passive"))
      (node (ref "R5") (pin "1") (pinfunction "1_1") (pintype "passive"))
      (node (ref "R6") (pin "1") (pinfunction "1_1") (pintype "passive"))
      (node (ref "R64") (pin "1") (pinfunction "1_1") (pintype "passive"))
      (node (ref "R65") (pin "1") (pinfunction "1_1") (pintype "passive"))
      (node (ref "R67") (pin "1") (pinfunction "1_1") (pintype "passive"))
      (node (ref "R70") (pin "1") (pinfunction "1_1") (pintype "passive"))
      (node (ref "R71") (pin "1") (pinfunction "1_1") (pintype "passive"))
      (node (ref "R72") (pin "1") (pinfunction "1_1") (pintype "passive"))
      (node (ref "R73") (pin "1") (pinfunction "1_1") (pintype "passive"))
      (node (ref "R75") (pin "2") (pinfunction "2_2") (pintype "passive"))
      (node (ref "R76") (pin "2") (pinfunction "2_2") (pintype "passive"))
      (node (ref "R77") (pin "1") (pinfunction "1_1") (pintype "passive"))
      (node (ref "R78") (pin "1") (pinfunction "1_1") (pintype "passive"))
      (node (ref "R8") (pin "1") (pinfunction "1_1") (pintype "passive"))
      (node (ref "R80") (pin "1") (pinfunction "1_1") (pintype "passive"))
      (node (ref "R81") (pin "1") (pinfunction "1_1") (pintype "passive"))
      (node (ref "R82") (pin "1") (pinfunction "1_1") (pintype "passive"))
      (node (ref "R83") (pin "1") (pinfunction "1_1") (pintype "passive"))
      (node (ref "U$2") (pin "4") (pinfunction "VDD_4") (pintype "power_in"))
      (node (ref "U10") (pin "3") (pinfunction "VCC_3") (pintype "power_in"))
      (node (ref "U12") (pin "4") (pinfunction "VDD_4") (pintype "power_in"))
      (node (ref "U13") (pin "4") (pinfunction "VDD_4") (pintype "power_in"))
      (node (ref "U14") (pin "4") (pinfunction "VDD_4") (pintype "power_in"))
      (node (ref "U6") (pin "4") (pinfunction "VDD_4") (pintype "power_in"))
      (node (ref "U8") (pin "2") (pinfunction "SREF_2") (pintype "bidirectional"))
      (node (ref "U9") (pin "2") (pinfunction "SDX_2") (pintype "bidirectional"))
      (node (ref "U9") (pin "3") (pinfunction "SCX_3") (pintype "bidirectional"))
      (node (ref "U9") (pin "5") (pinfunction "VDDIO_5") (pintype "bidirectional"))
      (node (ref "U9") (pin "8") (pinfunction "VDD_8") (pintype "bidirectional"))
      (node (ref "X1") (pin "2") (pinfunction "S_2") (pintype "passive"))
      (node (ref "XB1") (pin "1") (pinfunction "VCC_1") (pintype "power_in"))
      (node (ref "XB1") (pin "5") (pinfunction "~{RESET}_5") (pintype "input"))
    )
    (net (code "2") (name "5.0V") (class "Default")
      (node (ref "C36") (pin "1") (pinfunction "P$1_1") (pintype "passive"))
      (node (ref "C52") (pin "1") (pinfunction "P$1_1") (pintype "passive"))
      (node (ref "C9") (pin "1") (pinfunction "P$1_1") (pintype "passive"))
      (node (ref "J1") (pin "D3") (pinfunction "D_D3") (pintype "bidirectional"))
      (node (ref "J1") (pin "D4") (pinfunction "D_D4") (pintype "bidirectional"))
      (node (ref "J1") (pin "G4") (pinfunction "G_G4") (pintype "bidirectional"))
      (node (ref "J2") (pin "H4") (pinfunction "H_H4") (pintype "bidirectional"))
      (node (ref "J2") (pin "J4") (pinfunction "J_J4") (pintype "bidirectional"))
      (node (ref "J2") (pin "K1") (pinfunction "K_K1") (pintype "bidirectional"))
      (node (ref "J2") (pin "K2") (pinfunction "K_K2") (pintype "bidirectional"))
      (node (ref "J2") (pin "K3") (pinfunction "K_K3") (pintype "bidirectional"))
      (node (ref "J2") (pin "K4") (pinfunction "K_K4") (pintype "bidirectional"))
      (node (ref "R54") (pin "2") (pinfunction "2_2") (pintype "passive"))
      (node (ref "R55") (pin "1") (pinfunction "1_1") (pintype "passive"))
      (node (ref "R56") (pin "1") (pinfunction "1_1") (pintype "passive"))
      (node (ref "R57") (pin "1") (pinfunction "1_1") (pintype "passive"))
      (node (ref "R58") (pin "1") (pinfunction "1_1") (pintype "passive"))
      (node (ref "R59") (pin "1") (pinfunction "1_1") (pintype "passive"))
      (node (ref "R60") (pin "1") (pinfunction "1_1") (pintype "passive"))
      (node (ref "R61") (pin "1") (pinfunction "1_1") (pintype "passive"))
      (node (ref "R62") (pin "1") (pinfunction "1_1") (pintype "passive"))
      (node (ref "U$36") (pin "2") (pinfunction "VCC_2") (pintype "bidirectional"))
      (node (ref "U11") (pin "14") (pinfunction "VCC_14") (pintype "bidirectional"))
      (node (ref "U2") (pin "2") (pinfunction "OUT_2") (pintype "passive"))
      (node (ref "U5") (pin "14") (pinfunction "VCC_14") (pintype "bidirectional"))
      (node (ref "U7") (pin "5V") (pinfunction "5V_5V") (pintype "bidirectional"))
      (node (ref "X1") (pin "1") (pinfunction "S_1") (pintype "passive"))
    )
    (net (code "3") (name "12V") (class "Default")
      (node (ref "C10") (pin "1") (pinfunction "P$1_1") (pintype "passive"))
      (node (ref "C11") (pin "1") (pinfunction "P$1_1") (pintype "passive"))
      (node (ref "C2") (pin "1") (pinfunction "P$1_1") (pintype "passive"))
      (node (ref "C3") (pin "1") (pinfunction "P$1_1") (pintype "passive"))
      (node (ref "J1") (pin "A4") (pinfunction "A_A4") (pintype "bidirectional"))
      (node (ref "PTC2") (pin "P$1") (pinfunction "1_P$1") (pintype "passive"))
      (node (ref "R1") (pin "1") (pinfunction "1_1") (pintype "passive"))
      (node (ref "R38") (pin "1") (pinfunction "1_1") (pintype "passive"))
      (node (ref "U2") (pin "3") (pinfunction "IN_3") (pintype "input"))
      (node (ref "U3") (pin "2") (pinfunction "VIN_2") (pintype "input"))
      (node (ref "U4") (pin "3") (pinfunction "IN_3") (pintype "input"))
    )
    (net (code "4") (name "AUX2") (class "Default")
      (node (ref "J1") (pin "G3") (pinfunction "G_G3") (pintype "bidirectional"))
      (node (ref "R64") (pin "2") (pinfunction "2_2") (pintype "passive"))
      (node (ref "U8") (pin "37") (pinfunction "D10_37") (pintype "bidirectional"))
    )
    (net (code "5") (name "AUX2L") (class "Default")
      (node (ref "J3") (pin "75") (pinfunction "PA9_75") (pintype "bidirectional"))
      (node (ref "U8") (pin "12") (pinfunction "S10_12") (pintype "bidirectional"))
    )
    (net (code "6") (name "AUX3") (class "Default")
      (node (ref "J1") (pin "E4") (pinfunction "E_E4") (pintype "bidirectional"))
      (node (ref "R65") (pin "2") (pinfunction "2_2") (pintype "passive"))
      (node (ref "U8") (pin "36") (pinfunction "D11_36") (pintype "bidirectional"))
    )
    (net (code "7") (name "AUX3L") (class "Default")
      (node (ref "J3") (pin "63") (pinfunction "PD15_63") (pintype "bidirectional"))
      (node (ref "U8") (pin "13") (pinfunction "S11_13") (pintype "bidirectional"))
    )
    (net (code "8") (name "AUX4") (class "Default")
      (node (ref "J1") (pin "E3") (pinfunction "E_E3") (pintype "bidirectional"))
      (node (ref "R67") (pin "2") (pinfunction "2_2") (pintype "passive"))
      (node (ref "U8") (pin "35") (pinfunction "D12_35") (pintype "bidirectional"))
    )
    (net (code "9") (name "AUX4L") (class "Default")
      (node (ref "J3") (pin "61") (pinfunction "PD14_61") (pintype "bidirectional"))
      (node (ref "U8") (pin "14") (pinfunction "S12_14") (pintype "bidirectional"))
    )
    (net (code "10") (name "AUX5") (class "Default")
      (node (ref "J1") (pin "E1") (pinfunction "E_E1") (pintype "bidirectional"))
      (node (ref "R70") (pin "2") (pinfunction "2_2") (pintype "passive"))
      (node (ref "U8") (pin "34") (pinfunction "D13_34") (pintype "bidirectional"))
    )
    (net (code "11") (name "AUX5L") (class "Default")
      (node (ref "J3") (pin "59") (pinfunction "PD13_59") (pintype "bidirectional"))
      (node (ref "U8") (pin "15") (pinfunction "S13_15") (pintype "bidirectional"))
    )
    (net (code "12") (name "AUX6") (class "Default")
      (node (ref "J1") (pin "E2") (pinfunction "E_E2") (pintype "bidirectional"))
      (node (ref "R71") (pin "2") (pinfunction "2_2") (pintype "passive"))
      (node (ref "U8") (pin "33") (pinfunction "D14_33") (pintype "bidirectional"))
    )
    (net (code "13") (name "AUX6L") (class "Default")
      (node (ref "J3") (pin "57") (pinfunction "PD12_57") (pintype "bidirectional"))
      (node (ref "U8") (pin "16") (pinfunction "S14_16") (pintype "bidirectional"))
    )
    (net (code "14") (name "AUX7") (class "Default")
      (node (ref "J1") (pin "D1") (pinfunction "D_D1") (pintype "bidirectional"))
      (node (ref "R72") (pin "2") (pinfunction "2_2") (pintype "passive"))
      (node (ref "U8") (pin "32") (pinfunction "D15_32") (pintype "bidirectional"))
    )
    (net (code "15") (name "AUX7L") (class "Default")
      (node (ref "J3") (pin "55") (pinfunction "PD11_55") (pintype "bidirectional"))
      (node (ref "U8") (pin "17") (pinfunction "S15_17") (pintype "bidirectional"))
    )
    (net (code "16") (name "AUX8") (class "Default")
      (node (ref "J1") (pin "C3") (pinfunction "C_C3") (pintype "bidirectional"))
      (node (ref "R73") (pin "2") (pinfunction "2_2") (pintype "passive"))
      (node (ref "U8") (pin "31") (pinfunction "D16_31") (pintype "bidirectional"))
    )
    (net (code "17") (name "AUX8L") (class "Default")
      (node (ref "J3") (pin "53") (pinfunction "PD10_53") (pintype "bidirectional"))
      (node (ref "U8") (pin "18") (pinfunction "S16_18") (pintype "bidirectional"))
    )
    (net (code "18") (name "AUX9") (class "Default")
      (node (ref "J1") (pin "C2") (pinfunction "C_C2") (pintype "bidirectional"))
      (node (ref "R77") (pin "2") (pinfunction "2_2") (pintype "passive"))
      (node (ref "U8") (pin "30") (pinfunction "D17_30") (pintype "bidirectional"))
    )
    (net (code "19") (name "AUX9L") (class "Default")
      (node (ref "J3") (pin "51") (pinfunction "PD9_51") (pintype "bidirectional"))
      (node (ref "U8") (pin "19") (pinfunction "S17_19") (pintype "bidirectional"))
    )
    (net (code "20") (name "BITE") (class "Default")
      (node (ref "J1") (pin "A1") (pinfunction "A_A1") (pintype "bidirectional"))
    )
    (net (code "21") (name "BRAKEP") (class "Default")
      (node (ref "J2") (pin "F4") (pinfunction "F_F4") (pintype "bidirectional"))
      (node (ref "R19") (pin "2") (pinfunction "2_2") (pintype "passive"))
      (node (ref "U12") (pin "12") (pinfunction "VIND+_12") (pintype "input"))
    )
    (net (code "22") (name "BRAKEP2") (class "Default")
      (node (ref "J2") (pin "F2") (pinfunction "F_F2") (pintype "bidirectional"))
      (node (ref "R15") (pin "2") (pinfunction "2_2") (pintype "passive"))
      (node (ref "U13") (pin "3") (pinfunction "VINA+_3") (pintype "input"))
    )
    (net (code "23") (name "BRAKEP2B") (class "Default")
      (node (ref "J3") (pin "7") (pinfunction "PA6/AN6_7") (pintype "bidirectional"))
      (node (ref "U13") (pin "1") (pinfunction "VOUTA_1") (pintype "output"))
      (node (ref "U13") (pin "2") (pinfunction "VINA-_2") (pintype "input"))
    )
    (net (code "24") (name "BRAKEPB") (class "Default")
      (node (ref "J3") (pin "13") (pinfunction "PC5/AN15_13") (pintype "bidirectional"))
      (node (ref "U12") (pin "13") (pinfunction "VIND-_13") (pintype "input"))
      (node (ref "U12") (pin "14") (pinfunction "VOUTD_14") (pintype "output"))
    )
    (net (code "25") (name "CAN_N") (class "Default")
      (node (ref "J2") (pin "D1") (pinfunction "D_D1") (pintype "bidirectional"))
      (node (ref "SW1") (pin "P$2") (pinfunction "P1_P$2") (pintype "passive"))
      (node (ref "U10") (pin "6") (pinfunction "CANL_6") (pintype "output"))
      (node (ref "X1") (pin "8") (pinfunction "S_8") (pintype "passive"))
    )
    (net (code "26") (name "CAN_P") (class "Default")
      (node (ref "J2") (pin "D2") (pinfunction "D_D2") (pintype "bidirectional"))
      (node (ref "SW1") (pin "P$5") (pinfunction "P2_P$5") (pintype "passive"))
      (node (ref "U10") (pin "7") (pinfunction "CANH_7") (pintype "output"))
      (node (ref "X1") (pin "7") (pinfunction "S_7") (pintype "passive"))
    )
    (net (code "27") (name "CAN_RX") (class "Default")
      (node (ref "J3") (pin "93") (pinfunction "PD0_93") (pintype "bidirectional"))
      (node (ref "U10") (pin "4") (pinfunction "R_4") (pintype "output"))
    )
    (net (code "28") (name "CAN_TX") (class "Default")
      (node (ref "J3") (pin "95") (pinfunction "PD1_95") (pintype "bidirectional"))
      (node (ref "U10") (pin "1") (pinfunction "D_1") (pintype "input"))
    )
    (net (code "29") (name "CLUTCH-POT") (class "Default")
      (node (ref "J1") (pin "C4") (pinfunction "C_C4") (pintype "bidirectional"))
      (node (ref "R85") (pin "1") (pinfunction "1_1") (pintype "passive"))
    )
    (net (code "30") (name "CLUTCH-POTB") (class "Default")
      (node (ref "J3") (pin "153") (pinfunction "PA0/AN0_153") (pintype "bidirectional"))
      (node (ref "U14") (pin "13") (pinfunction "VIND-_13") (pintype "input"))
      (node (ref "U14") (pin "14") (pinfunction "VOUTD_14") (pintype "output"))
    )
    (net (code "31") (name "COM_RX") (class "Default")
      (node (ref "J2") (pin "C1") (pinfunction "C_C1") (pintype "bidirectional"))
      (node (ref "R81") (pin "2") (pinfunction "2_2") (pintype "passive"))
      (node (ref "U8") (pin "26") (pinfunction "D21_26") (pintype "bidirectional"))
    )
    (net (code "32") (name "COM_RXB") (class "Default")
      (node (ref "J3") (pin "67") (pinfunction "PC7_67") (pintype "bidirectional"))
      (node (ref "U8") (pin "23") (pinfunction "S21_23") (pintype "bidirectional"))
    )
    (net (code "33") (name "COM_TX") (class "Default")
      (node (ref "J2") (pin "C2") (pinfunction "C_C2") (pintype "bidirectional"))
      (node (ref "R82") (pin "2") (pinfunction "2_2") (pintype "passive"))
      (node (ref "U8") (pin "25") (pinfunction "D22_25") (pintype "bidirectional"))
    )
    (net (code "34") (name "COM_TXB") (class "Default")
      (node (ref "J3") (pin "65") (pinfunction "PC6_65") (pintype "bidirectional"))
      (node (ref "U8") (pin "24") (pinfunction "S22_24") (pintype "bidirectional"))
    )
    (net (code "35") (name "CS") (class "Default")
      (node (ref "J3") (pin "41") (pinfunction "PB12_41") (pintype "bidirectional"))
      (node (ref "U9") (pin "12") (pinfunction "CS_12") (pintype "bidirectional"))
    )
    (net (code "36") (name "CTS") (class "Default")
      (node (ref "J3") (pin "31") (pinfunction "PE13_31") (pintype "bidirectional"))
      (node (ref "U7") (pin "23") (pinfunction "P2_23") (pintype "bidirectional"))
      (node (ref "XB1") (pin "12") (pinfunction "~{CTS}/DIO7_12") (pintype "bidirectional"))
    )
    (net (code "37") (name "CURRENT1") (class "Default")
      (node (ref "J2") (pin "E1") (pinfunction "E_E1") (pintype "bidirectional"))
      (node (ref "R95") (pin "1") (pinfunction "1_1") (pintype "passive"))
    )
    (net (code "38") (name "CURRENT1B") (class "Default")
      (node (ref "J3") (pin "5") (pinfunction "PA5/AN5_5") (pintype "bidirectional"))
      (node (ref "U13") (pin "13") (pinfunction "VIND-_13") (pintype "input"))
      (node (ref "U13") (pin "14") (pinfunction "VOUTD_14") (pintype "output"))
    )
    (net (code "39") (name "CURRENT2") (class "Default")
      (node (ref "J2") (pin "E3") (pinfunction "E_E3") (pintype "bidirectional"))
      (node (ref "R94") (pin "1") (pinfunction "1_1") (pintype "passive"))
    )
    (net (code "40") (name "CURRENT2B") (class "Default")
      (node (ref "J3") (pin "1") (pinfunction "PA3/AN3_1") (pintype "bidirectional"))
      (node (ref "U13") (pin "8") (pinfunction "VOUTC_8") (pintype "output"))
      (node (ref "U13") (pin "9") (pinfunction "VINC-_9") (pintype "input"))
    )
    (net (code "41") (name "DBG_RX") (class "Default")
      (node (ref "J3") (pin "39") (pinfunction "PB11_39") (pintype "bidirectional"))
      (node (ref "J4") (pin "P$3") (pinfunction "RXI_P$3") (pintype "bidirectional"))
      (node (ref "X1") (pin "6") (pinfunction "S_6") (pintype "passive"))
    )
    (net (code "42") (name "DBG_TX") (class "Default")
      (node (ref "J3") (pin "37") (pinfunction "PB10_37") (pintype "bidirectional"))
      (node (ref "J4") (pin "P$2") (pinfunction "TXO_P$2") (pintype "bidirectional"))
      (node (ref "X1") (pin "5") (pinfunction "S_5") (pintype "passive"))
    )
    (net (code "43") (name "ECU1") (class "Default")
      (node (ref "J1") (pin "K2") (pinfunction "K_K2") (pintype "bidirectional"))
      (node (ref "R55") (pin "2") (pinfunction "2_2") (pintype "passive"))
      (node (ref "U8") (pin "46") (pinfunction "D1_46") (pintype "bidirectional"))
    )
    (net (code "44") (name "ECU1L") (class "Default")
      (node (ref "J3") (pin "123") (pinfunction "PE1_123") (pintype "bidirectional"))
      (node (ref "U8") (pin "3") (pinfunction "S1_3") (pintype "bidirectional"))
    )
    (net (code "45") (name "ECU2") (class "Default")
      (node (ref "J1") (pin "K1") (pinfunction "K_K1") (pintype "bidirectional"))
      (node (ref "R56") (pin "2") (pinfunction "2_2") (pintype "passive"))
      (node (ref "U8") (pin "45") (pinfunction "D2_45") (pintype "bidirectional"))
    )
    (net (code "46") (name "ECU2L") (class "Default")
      (node (ref "J3") (pin "121") (pinfunction "PE0_121") (pintype "bidirectional"))
      (node (ref "U8") (pin "4") (pinfunction "S2_4") (pintype "bidirectional"))
    )
    (net (code "47") (name "GEARPOSAN") (class "Default")
      (node (ref "J2") (pin "H3") (pinfunction "H_H3") (pintype "bidirectional"))
      (node (ref "R91") (pin "1") (pinfunction "1_1") (pintype "passive"))
    )
    (net (code "48") (name "GEARPOSANB") (class "Default")
      (node (ref "J3") (pin "17") (pinfunction "PB1/AN9_17") (pintype "bidirectional"))
      (node (ref "U12") (pin "6") (pinfunction "VINB-_6") (pintype "input"))
      (node (ref "U12") (pin "7") (pinfunction "VOUTB_7") (pintype "output"))
    )
    (net (code "49") (name "GND") (class "Default")
      (node (ref "C1") (pin "1") (pinfunction "P$1_1") (pintype "passive"))
      (node (ref "C10") (pin "2") (pinfunction "P$2_2") (pintype "passive"))
      (node (ref "C11") (pin "2") (pinfunction "P$2_2") (pintype "passive"))
      (node (ref "C12") (pin "1") (pinfunction "P$1_1") (pintype "passive"))
      (node (ref "C13") (pin "2") (pinfunction "P$2_2") (pintype "passive"))
      (node (ref "C16") (pin "2") (pinfunction "P$2_2") (pintype "passive"))
      (node (ref "C17") (pin "2") (pinfunction "P$2_2") (pintype "passive"))
      (node (ref "C19") (pin "2") (pinfunction "P$2_2") (pintype "passive"))
      (node (ref "C2") (pin "2") (pinfunction "P$2_2") (pintype "passive"))
      (node (ref "C20") (pin "2") (pinfunction "P$2_2") (pintype "passive"))
      (node (ref "C21") (pin "1") (pinfunction "P$1_1") (pintype "passive"))
      (node (ref "C22") (pin "1") (pinfunction "P$1_1") (pintype "passive"))
      (node (ref "C23") (pin "1") (pinfunction "P$1_1") (pintype "passive"))
      (node (ref "C24") (pin "2") (pinfunction "P$2_2") (pintype "passive"))
      (node (ref "C25") (pin "2") (pinfunction "P$2_2") (pintype "passive"))
      (node (ref "C26") (pin "2") (pinfunction "P$2_2") (pintype "passive"))
      (node (ref "C27") (pin "2") (pinfunction "P$2_2") (pintype "passive"))
      (node (ref "C28") (pin "2") (pinfunction "P$2_2") (pintype "passive"))
      (node (ref "C3") (pin "2") (pinfunction "P$2_2") (pintype "passive"))
      (node (ref "C36") (pin "2") (pinfunction "P$2_2") (pintype "passive"))
      (node (ref "C4") (pin "P$3") (pinfunction "P$2_P$3") (pintype "bidirectional"))
      (node (ref "C41") (pin "2") (pinfunction "P$2_2") (pintype "passive"))
      (node (ref "C50") (pin "2") (pinfunction "P$2_2") (pintype "passive"))
      (node (ref "C52") (pin "2") (pinfunction "P$2_2") (pintype "passive"))
      (node (ref "C6") (pin "2") (pinfunction "P$2_2") (pintype "passive"))
      (node (ref "C7") (pin "2") (pinfunction "P$2_2") (pintype "passive"))
      (node (ref "C8") (pin "2") (pinfunction "P$2_2") (pintype "passive"))
      (node (ref "C9") (pin "2") (pinfunction "P$2_2") (pintype "passive"))
      (node (ref "CN1") (pin "GND") (pinfunction "GND_GND") (pintype "power_in"))
      (node (ref "D1") (pin "A") (pinfunction "A_A") (pintype "passive"))
      (node (ref "D10") (pin "A") (pinfunction "A_A") (pintype "passive"))
      (node (ref "D11") (pin "A") (pinfunction "A_A") (pintype "passive"))
      (node (ref "D2") (pin "A") (pinfunction "A_A") (pintype "passive"))
      (node (ref "D3") (pin "A") (pinfunction "A_A") (pintype "passive"))
      (node (ref "D8") (pin "A") (pinfunction "A_A") (pintype "passive"))
      (node (ref "D9") (pin "A") (pinfunction "A_A") (pintype "passive"))
      (node (ref "J1") (pin "B1") (pinfunction "B_B1") (pintype "bidirectional"))
      (node (ref "J1") (pin "B2") (pinfunction "B_B2") (pintype "bidirectional"))
      (node (ref "J1") (pin "B3") (pinfunction "B_B3") (pintype "bidirectional"))
      (node (ref "J1") (pin "B4") (pinfunction "B_B4") (pintype "bidirectional"))
      (node (ref "J1") (pin "D2") (pinfunction "D_D2") (pintype "bidirectional"))
      (node (ref "J1") (pin "F1") (pinfunction "F_F1") (pintype "bidirectional"))
      (node (ref "J1") (pin "F2") (pinfunction "F_F2") (pintype "bidirectional"))
      (node (ref "J1") (pin "F3") (pinfunction "F_F3") (pintype "bidirectional"))
      (node (ref "J1") (pin "F4") (pinfunction "F_F4") (pintype "bidirectional"))
      (node (ref "J1") (pin "G1") (pinfunction "G_G1") (pintype "bidirectional"))
      (node (ref "J1") (pin "H4") (pinfunction "H_H4") (pintype "bidirectional"))
      (node (ref "J1") (pin "J1") (pinfunction "J_J1") (pintype "bidirectional"))
      (node (ref "J1") (pin "M4") (pinfunction "M_M4") (pintype "bidirectional"))
      (node (ref "J2") (pin "C3") (pinfunction "C_C3") (pintype "bidirectional"))
      (node (ref "J2") (pin "D3") (pinfunction "D_D3") (pintype "bidirectional"))
      (node (ref "J2") (pin "E2") (pinfunction "E_E2") (pintype "bidirectional"))
      (node (ref "J2") (pin "E4") (pinfunction "E_E4") (pintype "bidirectional"))
      (node (ref "J2") (pin "G1") (pinfunction "G_G1") (pintype "bidirectional"))
      (node (ref "J2") (pin "G2") (pinfunction "G_G2") (pintype "bidirectional"))
      (node (ref "J2") (pin "G3") (pinfunction "G_G3") (pintype "bidirectional"))
      (node (ref "J2") (pin "G4") (pinfunction "G_G4") (pintype "bidirectional"))
      (node (ref "J2") (pin "H2") (pinfunction "H_H2") (pintype "bidirectional"))
      (node (ref "J2") (pin "J2") (pinfunction "J_J2") (pintype "bidirectional"))
      (node (ref "J2") (pin "M1") (pinfunction "M_M1") (pintype "bidirectional"))
      (node (ref "J2") (pin "M2") (pinfunction "M_M2") (pintype "bidirectional"))
      (node (ref "J2") (pin "M3") (pinfunction "M_M3") (pintype "bidirectional"))
      (node (ref "J2") (pin "M4") (pinfunction "M_M4") (pintype "bidirectional"))
      (node (ref "J3") (pin "10") (pinfunction "GND_10") (pintype "bidirectional"))
      (node (ref "J3") (pin "100") (pinfunction "GND_100") (pintype "bidirectional"))
      (node (ref "J3") (pin "102") (pinfunction "GND_102") (pintype "bidirectional"))
      (node (ref "J3") (pin "104") (pinfunction "GND_104") (pintype "bidirectional"))
      (node (ref "J3") (pin "106") (pinfunction "GND_106") (pintype "bidirectional"))
      (node (ref "J3") (pin "108") (pinfunction "GND_108") (pintype "bidirectional"))
      (node (ref "J3") (pin "110") (pinfunction "GND_110") (pintype "bidirectional"))
      (node (ref "J3") (pin "112") (pinfunction "GND_112") (pintype "bidirectional"))
      (node (ref "J3") (pin "114") (pinfunction "GND_114") (pintype "bidirectional"))
      (node (ref "J3") (pin "116") (pinfunction "GND_116") (pintype "bidirectional"))
      (node (ref "J3") (pin "118") (pinfunction "GND_118") (pintype "bidirectional"))
      (node (ref "J3") (pin "12") (pinfunction "GND_12") (pintype "bidirectional"))
      (node (ref "J3") (pin "120") (pinfunction "GND_120") (pintype "bidirectional"))
      (node (ref "J3") (pin "122") (pinfunction "GND_122") (pintype "bidirectional"))
      (node (ref "J3") (pin "124") (pinfunction "GND_124") (pintype "bidirectional"))
      (node (ref "J3") (pin "125") (pinfunction "GND_125") (pintype "bidirectional"))
      (node (ref "J3") (pin "126") (pinfunction "GND_126") (pintype "bidirectional"))
      (node (ref "J3") (pin "127") (pinfunction "GND_127") (pintype "bidirectional"))
      (node (ref "J3") (pin "128") (pinfunction "GND_128") (pintype "bidirectional"))
      (node (ref "J3") (pin "129") (pinfunction "GND_129") (pintype "bidirectional"))
      (node (ref "J3") (pin "130") (pinfunction "GND_130") (pintype "bidirectional"))
      (node (ref "J3") (pin "131") (pinfunction "GND_131") (pintype "bidirectional"))
      (node (ref "J3") (pin "132") (pinfunction "GND_132") (pintype "bidirectional"))
      (node (ref "J3") (pin "134") (pinfunction "GND_134") (pintype "bidirectional"))
      (node (ref "J3") (pin "136") (pinfunction "GND_136") (pintype "bidirectional"))
      (node (ref "J3") (pin "138") (pinfunction "GND_138") (pintype "bidirectional"))
      (node (ref "J3") (pin "14") (pinfunction "GND_14") (pintype "bidirectional"))
      (node (ref "J3") (pin "140") (pinfunction "GND_140") (pintype "bidirectional"))
      (node (ref "J3") (pin "142") (pinfunction "GND_142") (pintype "bidirectional"))
      (node (ref "J3") (pin "144") (pinfunction "GND_144") (pintype "bidirectional"))
      (node (ref "J3") (pin "146") (pinfunction "GND_146") (pintype "bidirectional"))
      (node (ref "J3") (pin "148") (pinfunction "GND_148") (pintype "bidirectional"))
      (node (ref "J3") (pin "150") (pinfunction "GND_150") (pintype "bidirectional"))
      (node (ref "J3") (pin "152") (pinfunction "GND_152") (pintype "bidirectional"))
      (node (ref "J3") (pin "154") (pinfunction "GND_154") (pintype "bidirectional"))
      (node (ref "J3") (pin "156") (pinfunction "GND_156") (pintype "bidirectional"))
      (node (ref "J3") (pin "158") (pinfunction "GND_158") (pintype "bidirectional"))
      (node (ref "J3") (pin "159") (pinfunction "GND_159") (pintype "bidirectional"))
      (node (ref "J3") (pin "16") (pinfunction "GND_16") (pintype "bidirectional"))
      (node (ref "J3") (pin "160") (pinfunction "GND_160") (pintype "bidirectional"))
      (node (ref "J3") (pin "161") (pinfunction "GND_161") (pintype "bidirectional"))
      (node (ref "J3") (pin "162") (pinfunction "GND_162") (pintype "bidirectional"))
      (node (ref "J3") (pin "163") (pinfunction "GND_163") (pintype "bidirectional"))
      (node (ref "J3") (pin "164") (pinfunction "GND_164") (pintype "bidirectional"))
      (node (ref "J3") (pin "165") (pinfunction "GND_165") (pintype "bidirectional"))
      (node (ref "J3") (pin "166") (pinfunction "GND_166") (pintype "bidirectional"))
      (node (ref "J3") (pin "167") (pinfunction "GND_167") (pintype "bidirectional"))
      (node (ref "J3") (pin "168") (pinfunction "GND_168") (pintype "bidirectional"))
      (node (ref "J3") (pin "169") (pinfunction "GND_169") (pintype "bidirectional"))
      (node (ref "J3") (pin "170") (pinfunction "GND_170") (pintype "bidirectional"))
      (node (ref "J3") (pin "171") (pinfunction "GND_171") (pintype "bidirectional"))
      (node (ref "J3") (pin "172") (pinfunction "GND_172") (pintype "bidirectional"))
      (node (ref "J3") (pin "173") (pinfunction "GND_173") (pintype "bidirectional"))
      (node (ref "J3") (pin "174") (pinfunction "GND_174") (pintype "bidirectional"))
      (node (ref "J3") (pin "175") (pinfunction "GND_175") (pintype "bidirectional"))
      (node (ref "J3") (pin "176") (pinfunction "GND_176") (pintype "bidirectional"))
      (node (ref "J3") (pin "177") (pinfunction "GND_177") (pintype "bidirectional"))
      (node (ref "J3") (pin "178") (pinfunction "GND_178") (pintype "bidirectional"))
      (node (ref "J3") (pin "179") (pinfunction "GND_179") (pintype "bidirectional"))
      (node (ref "J3") (pin "18") (pinfunction "GND_18") (pintype "bidirectional"))
      (node (ref "J3") (pin "180") (pinfunction "GND_180") (pintype "bidirectional"))
      (node (ref "J3") (pin "181") (pinfunction "GND_181") (pintype "bidirectional"))
      (node (ref "J3") (pin "182") (pinfunction "GND_182") (pintype "bidirectional"))
      (node (ref "J3") (pin "183") (pinfunction "GND_183") (pintype "bidirectional"))
      (node (ref "J3") (pin "184") (pinfunction "GND_184") (pintype "bidirectional"))
      (node (ref "J3") (pin "185") (pinfunction "GND_185") (pintype "bidirectional"))
      (node (ref "J3") (pin "186") (pinfunction "GND_186") (pintype "bidirectional"))
      (node (ref "J3") (pin "187") (pinfunction "GND_187") (pintype "bidirectional"))
      (node (ref "J3") (pin "188") (pinfunction "GND_188") (pintype "bidirectional"))
      (node (ref "J3") (pin "189") (pinfunction "GND_189") (pintype "bidirectional"))
      (node (ref "J3") (pin "190") (pinfunction "GND_190") (pintype "bidirectional"))
      (node (ref "J3") (pin "191") (pinfunction "GND_191") (pintype "bidirectional"))
      (node (ref "J3") (pin "192") (pinfunction "GND_192") (pintype "bidirectional"))
      (node (ref "J3") (pin "193") (pinfunction "GND_193") (pintype "bidirectional"))
      (node (ref "J3") (pin "194") (pinfunction "GND_194") (pintype "bidirectional"))
      (node (ref "J3") (pin "195") (pinfunction "GND_195") (pintype "bidirectional"))
      (node (ref "J3") (pin "196") (pinfunction "GND_196") (pintype "bidirectional"))
      (node (ref "J3") (pin "198") (pinfunction "GND_198") (pintype "bidirectional"))
      (node (ref "J3") (pin "2") (pinfunction "GND_2") (pintype "bidirectional"))
      (node (ref "J3") (pin "20") (pinfunction "GND_20") (pintype "bidirectional"))
      (node (ref "J3") (pin "200") (pinfunction "GND_200") (pintype "bidirectional"))
      (node (ref "J3") (pin "22") (pinfunction "GND_22") (pintype "bidirectional"))
      (node (ref "J3") (pin "24") (pinfunction "GND_24") (pintype "bidirectional"))
      (node (ref "J3") (pin "26") (pinfunction "GND_26") (pintype "bidirectional"))
      (node (ref "J3") (pin "28") (pinfunction "GND_28") (pintype "bidirectional"))
      (node (ref "J3") (pin "30") (pinfunction "GND_30") (pintype "bidirectional"))
      (node (ref "J3") (pin "32") (pinfunction "GND_32") (pintype "bidirectional"))
      (node (ref "J3") (pin "34") (pinfunction "GND_34") (pintype "bidirectional"))
      (node (ref "J3") (pin "36") (pinfunction "GND_36") (pintype "bidirectional"))
      (node (ref "J3") (pin "38") (pinfunction "GND_38") (pintype "bidirectional"))
      (node (ref "J3") (pin "4") (pinfunction "GND_4") (pintype "bidirectional"))
      (node (ref "J3") (pin "40") (pinfunction "GND_40") (pintype "bidirectional"))
      (node (ref "J3") (pin "42") (pinfunction "GND_42") (pintype "bidirectional"))
      (node (ref "J3") (pin "44") (pinfunction "GND_44") (pintype "bidirectional"))
      (node (ref "J3") (pin "46") (pinfunction "GND_46") (pintype "bidirectional"))
      (node (ref "J3") (pin "48") (pinfunction "GND_48") (pintype "bidirectional"))
      (node (ref "J3") (pin "50") (pinfunction "GND_50") (pintype "bidirectional"))
      (node (ref "J3") (pin "52") (pinfunction "GND_52") (pintype "bidirectional"))
      (node (ref "J3") (pin "54") (pinfunction "GND_54") (pintype "bidirectional"))
      (node (ref "J3") (pin "56") (pinfunction "GND_56") (pintype "bidirectional"))
      (node (ref "J3") (pin "58") (pinfunction "GND_58") (pintype "bidirectional"))
      (node (ref "J3") (pin "6") (pinfunction "GND_6") (pintype "bidirectional"))
      (node (ref "J3") (pin "60") (pinfunction "GND_60") (pintype "bidirectional"))
      (node (ref "J3") (pin "62") (pinfunction "GND_62") (pintype "bidirectional"))
      (node (ref "J3") (pin "64") (pinfunction "GND_64") (pintype "bidirectional"))
      (node (ref "J3") (pin "66") (pinfunction "GND_66") (pintype "bidirectional"))
      (node (ref "J3") (pin "68") (pinfunction "GND_68") (pintype "bidirectional"))
      (node (ref "J3") (pin "70") (pinfunction "GND_70") (pintype "bidirectional"))
      (node (ref "J3") (pin "77") (pinfunction "GND_77") (pintype "bidirectional"))
      (node (ref "J3") (pin "78") (pinfunction "GND_78") (pintype "bidirectional"))
      (node (ref "J3") (pin "79") (pinfunction "GND_79") (pintype "bidirectional"))
      (node (ref "J3") (pin "8") (pinfunction "GND_8") (pintype "bidirectional"))
      (node (ref "J3") (pin "80") (pinfunction "GND_80") (pintype "bidirectional"))
      (node (ref "J3") (pin "81") (pinfunction "GND_81") (pintype "bidirectional"))
      (node (ref "J3") (pin "83") (pinfunction "GND_83") (pintype "bidirectional"))
      (node (ref "J3") (pin "85") (pinfunction "GND_85") (pintype "bidirectional"))
      (node (ref "J3") (pin "92") (pinfunction "GND_92") (pintype "bidirectional"))
      (node (ref "J3") (pin "94") (pinfunction "GND_94") (pintype "bidirectional"))
      (node (ref "J3") (pin "96") (pinfunction "GND_96") (pintype "bidirectional"))
      (node (ref "J3") (pin "98") (pinfunction "GND_98") (pintype "bidirectional"))
      (node (ref "J4") (pin "P$6") (pinfunction "GND_P$6") (pintype "bidirectional"))
      (node (ref "JTAG1") (pin "10") (pinfunction "10_10") (pintype "passive"))
      (node (ref "JTAG1") (pin "12") (pinfunction "12_12") (pintype "passive"))
      (node (ref "JTAG1") (pin "14") (pinfunction "14_14") (pintype "passive"))
      (node (ref "JTAG1") (pin "16") (pinfunction "16_16") (pintype "passive"))
      (node (ref "JTAG1") (pin "18") (pinfunction "18_18") (pintype "passive"))
      (node (ref "JTAG1") (pin "20") (pinfunction "20_20") (pintype "passive"))
      (node (ref "JTAG1") (pin "3") (pinfunction "3_3") (pintype "passive"))
      (node (ref "JTAG1") (pin "4") (pinfunction "4_4") (pintype "passive"))
      (node (ref "JTAG1") (pin "6") (pinfunction "6_6") (pintype "passive"))
      (node (ref "JTAG1") (pin "8") (pinfunction "8_8") (pintype "passive"))
      (node (ref "OK1") (pin "2") (pinfunction "C_2") (pintype "passive"))
      (node (ref "OK1") (pin "4") (pinfunction "E_4") (pintype "passive"))
      (node (ref "Q1") (pin "2") (pinfunction "E_2") (pintype "passive"))
      (node (ref "Q2") (pin "2") (pinfunction "E_2") (pintype "passive"))
      (node (ref "Q3") (pin "2") (pinfunction "E_2") (pintype "passive"))
      (node (ref "Q5") (pin "2") (pinfunction "E_2") (pintype "passive"))
      (node (ref "Q6") (pin "2") (pinfunction "E_2") (pintype "passive"))
      (node (ref "Q7") (pin "2") (pinfunction "E_2") (pintype "passive"))
      (node (ref "Q8") (pin "2") (pinfunction "E_2") (pintype "passive"))
      (node (ref "R10") (pin "2") (pinfunction "2_2") (pintype "passive"))
      (node (ref "R103") (pin "1") (pinfunction "1_1") (pintype "passive"))
      (node (ref "R16") (pin "2") (pinfunction "2_2") (pintype "passive"))
      (node (ref "R2") (pin "2") (pinfunction "2_2") (pintype "passive"))
      (node (ref "R20") (pin "1") (pinfunction "1_1") (pintype "passive"))
      (node (ref "R23") (pin "1") (pinfunction "1_1") (pintype "passive"))
      (node (ref "R32") (pin "1") (pinfunction "1_1") (pintype "passive"))
      (node (ref "R33") (pin "1") (pinfunction "1_1") (pintype "passive"))
      (node (ref "R34") (pin "1") (pinfunction "1_1") (pintype "passive"))
      (node (ref "R35") (pin "1") (pinfunction "1_1") (pintype "passive"))
      (node (ref "R48") (pin "2") (pinfunction "2_2") (pintype "passive"))
      (node (ref "R49") (pin "2") (pinfunction "2_2") (pintype "passive"))
      (node (ref "R52") (pin "2") (pinfunction "2_2") (pintype "passive"))
      (node (ref "R53") (pin "2") (pinfunction "2_2") (pintype "passive"))
      (node (ref "R66") (pin "2") (pinfunction "2_2") (pintype "passive"))
      (node (ref "R69") (pin "2") (pinfunction "2_2") (pintype "passive"))
      (node (ref "R86") (pin "1") (pinfunction "1_1") (pintype "passive"))
      (node (ref "R87") (pin "1") (pinfunction "1_1") (pintype "passive"))
      (node (ref "R88") (pin "1") (pinfunction "1_1") (pintype "passive"))
      (node (ref "R89") (pin "1") (pinfunction "1_1") (pintype "passive"))
      (node (ref "R9") (pin "2") (pinfunction "2_2") (pintype "passive"))
      (node (ref "R92") (pin "1") (pinfunction "1_1") (pintype "passive"))
      (node (ref "R93") (pin "1") (pinfunction "1_1") (pintype "passive"))
      (node (ref "R96") (pin "1") (pinfunction "1_1") (pintype "passive"))
      (node (ref "R97") (pin "1") (pinfunction "1_1") (pintype "passive"))
      (node (ref "U$1") (pin "6") (pinfunction "AGND_6") (pintype "bidirectional"))
      (node (ref "U$1") (pin "7") (pinfunction "GND_7") (pintype "bidirectional"))
      (node (ref "U$2") (pin "6") (pinfunction "VSS_6") (pintype "power_in"))
      (node (ref "U$2") (pin "MT1") (pinfunction "GND_MT1") (pintype "power_in"))
      (node (ref "U$2") (pin "MT2") (pinfunction "GND1_MT2") (pintype "power_in"))
      (node (ref "U$36") (pin "1") (pinfunction "GND1_1") (pintype "bidirectional"))
      (node (ref "U$36") (pin "5") (pinfunction "GND2_5") (pintype "bidirectional"))
      (node (ref "U1") (pin "4") (pinfunction "G_4") (pintype "passive"))
      (node (ref "U10") (pin "2") (pinfunction "GND_2") (pintype "passive"))
      (node (ref "U11") (pin "1") (pinfunction "INT_THRS1_1") (pintype "bidirectional"))
      (node (ref "U11") (pin "11") (pinfunction "GND_11") (pintype "bidirectional"))
      (node (ref "U11") (pin "13") (pinfunction "ZERO_EN_13") (pintype "bidirectional"))
      (node (ref "U11") (pin "3") (pinfunction "BIAS1_3") (pintype "bidirectional"))
      (node (ref "U11") (pin "6") (pinfunction "BIAS2_6") (pintype "bidirectional"))
      (node (ref "U11") (pin "8") (pinfunction "INT_THRS2_8") (pintype "bidirectional"))
      (node (ref "U12") (pin "11") (pinfunction "VSS_11") (pintype "passive"))
      (node (ref "U13") (pin "11") (pinfunction "VSS_11") (pintype "passive"))
      (node (ref "U14") (pin "11") (pinfunction "VSS_11") (pintype "passive"))
      (node (ref "U2") (pin "1") (pinfunction "ADJ_1") (pintype "input"))
      (node (ref "U3") (pin "7") (pinfunction "GND_7") (pintype "passive"))
      (node (ref "U4") (pin "1") (pinfunction "ADJ_1") (pintype "input"))
      (node (ref "U5") (pin "1") (pinfunction "INT_THRS1_1") (pintype "bidirectional"))
      (node (ref "U5") (pin "11") (pinfunction "GND_11") (pintype "bidirectional"))
      (node (ref "U5") (pin "13") (pinfunction "ZERO_EN_13") (pintype "bidirectional"))
      (node (ref "U5") (pin "3") (pinfunction "BIAS1_3") (pintype "bidirectional"))
      (node (ref "U5") (pin "6") (pinfunction "BIAS2_6") (pintype "bidirectional"))
      (node (ref "U5") (pin "8") (pinfunction "INT_THRS2_8") (pintype "bidirectional"))
      (node (ref "U6") (pin "11") (pinfunction "VSS_11") (pintype "passive"))
      (node (ref "U7") (pin "GND") (pinfunction "GND_GND") (pintype "bidirectional"))
      (node (ref "U8") (pin "1") (pinfunction "GND_1") (pintype "bidirectional"))
      (node (ref "U9") (pin "6") (pinfunction "GND_6") (pintype "bidirectional"))
      (node (ref "U9") (pin "7") (pinfunction "GND_7") (pintype "bidirectional"))
      (node (ref "X1") (pin "14") (pinfunction "S_14") (pintype "passive"))
      (node (ref "X1") (pin "4") (pinfunction "S_4") (pintype "passive"))
      (node (ref "XB1") (pin "10") (pinfunction "GND_10") (pintype "power_in"))
    )
    (net (code "50") (name "GPS_RX") (class "Default")
      (node (ref "J3") (pin "115") (pinfunction "PB7_115") (pintype "bidirectional"))
      (node (ref "R21") (pin "1") (pinfunction "1_1") (pintype "passive"))
      (node (ref "R23") (pin "2") (pinfunction "2_2") (pintype "passive"))
    )
    (net (code "51") (name "GPS_TX") (class "Default")
      (node (ref "J3") (pin "113") (pinfunction "PB6_113") (pintype "bidirectional"))
      (node (ref "U$36") (pin "3") (pinfunction "RX_3") (pintype "bidirectional"))
    )
    (net (code "52") (name "GSENS") (class "Default")
      (node (ref "J1") (pin "A2") (pinfunction "A_A2") (pintype "bidirectional"))
      (node (ref "R45") (pin "1") (pinfunction "1_1") (pintype "passive"))
    )
    (net (code "53") (name "GSENSB") (class "Default")
      (node (ref "J3") (pin "157") (pinfunction "PA2/AN2_157") (pintype "bidirectional"))
      (node (ref "U14") (pin "6") (pinfunction "VINB-_6") (pintype "input"))
      (node (ref "U14") (pin "7") (pinfunction "VOUTB_7") (pintype "output"))
    )
    (net (code "54") (name "HB1-DIRA") (class "Default")
      (node (ref "J3") (pin "101") (pinfunction "PD4_101") (pintype "bidirectional"))
      (node (ref "U8") (pin "10") (pinfunction "S8_10") (pintype "bidirectional"))
    )
    (net (code "55") (name "HB1-DIRA-OUT") (class "Default")
      (node (ref "J1") (pin "H1") (pinfunction "H_H1") (pintype "bidirectional"))
      (node (ref "R62") (pin "2") (pinfunction "2_2") (pintype "passive"))
      (node (ref "U8") (pin "39") (pinfunction "D8_39") (pintype "bidirectional"))
    )
    (net (code "56") (name "HB1-DIRB") (class "Default")
      (node (ref "J3") (pin "109") (pinfunction "PB4_109") (pintype "bidirectional"))
      (node (ref "U8") (pin "8") (pinfunction "S6_8") (pintype "bidirectional"))
    )
    (net (code "57") (name "HB1-DIRB-OUT") (class "Default")
      (node (ref "J1") (pin "J4") (pinfunction "J_J4") (pintype "bidirectional"))
      (node (ref "R60") (pin "2") (pinfunction "2_2") (pintype "passive"))
      (node (ref "U8") (pin "41") (pinfunction "D6_41") (pintype "bidirectional"))
    )
    (net (code "58") (name "HB1-PWM") (class "Default")
      (node (ref "J3") (pin "119") (pinfunction "PB9_119") (pintype "bidirectional"))
      (node (ref "U8") (pin "5") (pinfunction "S3_5") (pintype "bidirectional"))
    )
    (net (code "59") (name "HB1-PWM-OUT") (class "Default")
      (node (ref "J1") (pin "J3") (pinfunction "J_J3") (pintype "bidirectional"))
      (node (ref "R57") (pin "2") (pinfunction "2_2") (pintype "passive"))
      (node (ref "U8") (pin "44") (pinfunction "D3_44") (pintype "bidirectional"))
    )
    (net (code "60") (name "HB2-DIRA") (class "Default")
      (node (ref "J3") (pin "107") (pinfunction "PD7_107") (pintype "bidirectional"))
      (node (ref "U8") (pin "9") (pinfunction "S7_9") (pintype "bidirectional"))
    )
    (net (code "61") (name "HB2-DIRA-OUT") (class "Default")
      (node (ref "J1") (pin "K3") (pinfunction "K_K3") (pintype "bidirectional"))
      (node (ref "R61") (pin "2") (pinfunction "2_2") (pintype "passive"))
      (node (ref "U8") (pin "40") (pinfunction "D7_40") (pintype "bidirectional"))
    )
    (net (code "62") (name "HB2-DIRB") (class "Default")
      (node (ref "J3") (pin "111") (pinfunction "PB5_111") (pintype "bidirectional"))
      (node (ref "U8") (pin "7") (pinfunction "S5_7") (pintype "bidirectional"))
    )
    (net (code "63") (name "HB2-DIRB-OUT") (class "Default")
      (node (ref "J1") (pin "K4") (pinfunction "K_K4") (pintype "bidirectional"))
      (node (ref "R59") (pin "2") (pinfunction "2_2") (pintype "passive"))
      (node (ref "U8") (pin "42") (pinfunction "D5_42") (pintype "bidirectional"))
    )
    (net (code "64") (name "HB2-PWM") (class "Default")
      (node (ref "J3") (pin "117") (pinfunction "PB8_117") (pintype "bidirectional"))
      (node (ref "U8") (pin "6") (pinfunction "S4_6") (pintype "bidirectional"))
    )
    (net (code "65") (name "HB2-PWM-OUT") (class "Default")
      (node (ref "J1") (pin "J2") (pinfunction "J_J2") (pintype "bidirectional"))
      (node (ref "R58") (pin "2") (pinfunction "2_2") (pintype "passive"))
      (node (ref "U8") (pin "43") (pinfunction "D4_43") (pintype "bidirectional"))
    )
    (net (code "66") (name "IGNCUT") (class "Default")
      (node (ref "J3") (pin "21") (pinfunction "PE8_21") (pintype "bidirectional"))
      (node (ref "R17") (pin "2") (pinfunction "2_2") (pintype "passive"))
    )
    (net (code "67") (name "IGNCUTO") (class "Default")
      (node (ref "J2") (pin "H1") (pinfunction "H_H1") (pintype "bidirectional"))
      (node (ref "Q3") (pin "3") (pinfunction "C_3") (pintype "passive"))
    )
    (net (code "68") (name "JTAG_TCK") (class "Default")
      (node (ref "J3") (pin "84") (pinfunction "TCK_84") (pintype "bidirectional"))
      (node (ref "JTAG1") (pin "9") (pinfunction "9_9") (pintype "passive"))
    )
    (net (code "69") (name "JTAG_TDI") (class "Default")
      (node (ref "J3") (pin "86") (pinfunction "TDI_86") (pintype "bidirectional"))
      (node (ref "JTAG1") (pin "5") (pinfunction "5_5") (pintype "passive"))
    )
    (net (code "70") (name "JTAG_TDO") (class "Default")
      (node (ref "J3") (pin "88") (pinfunction "TDO_88") (pintype "bidirectional"))
      (node (ref "JTAG1") (pin "13") (pinfunction "13_13") (pintype "passive"))
    )
    (net (code "71") (name "JTAG_TMS") (class "Default")
      (node (ref "J3") (pin "82") (pinfunction "TMS_82") (pintype "bidirectional"))
      (node (ref "JTAG1") (pin "7") (pinfunction "7_7") (pintype "passive"))
    )
    (net (code "72") (name "MISO") (class "Default")
      (node (ref "J3") (pin "45") (pinfunction "PB14_45") (pintype "bidirectional"))
      (node (ref "U7") (pin "38") (pinfunction "MISO_38") (pintype "bidirectional"))
      (node (ref "U9") (pin "1") (pinfunction "SDO/SA0_1") (pintype "bidirectional"))
      (node (ref "X1") (pin "12") (pinfunction "S_12") (pintype "passive"))
    )
    (net (code "73") (name "MOSI") (class "Default")
      (node (ref "J3") (pin "47") (pinfunction "PB15_47") (pintype "bidirectional"))
      (node (ref "U7") (pin "16") (pinfunction "MOSI_16") (pintype "bidirectional"))
      (node (ref "U9") (pin "14") (pinfunction "SDA_14") (pintype "bidirectional"))
      (node (ref "X1") (pin "11") (pinfunction "S_11") (pintype "passive"))
    )
    (net (code "74") (name "NEUTRAL") (class "Default")
      (node (ref "J2") (pin "J1") (pinfunction "J_J1") (pintype "bidirectional"))
      (node (ref "R37") (pin "2") (pinfunction "2_2") (pintype "passive"))
      (node (ref "R80") (pin "2") (pinfunction "2_2") (pintype "passive"))
      (node (ref "U8") (pin "27") (pinfunction "D20_27") (pintype "bidirectional"))
    )
    (net (code "75") (name "NEUTRALL") (class "Default")
      (node (ref "J3") (pin "35") (pinfunction "PE15_35") (pintype "bidirectional"))
      (node (ref "U8") (pin "22") (pinfunction "S20_22") (pintype "bidirectional"))
    )
    (net (code "76") (name "Net-(C1-P$2)") (class "Default")
      (node (ref "C1") (pin "2") (pinfunction "P$2_2") (pintype "passive"))
      (node (ref "R26") (pin "1") (pinfunction "1_1") (pintype "passive"))
      (node (ref "R63") (pin "2") (pinfunction "2_2") (pintype "passive"))
    )
    (net (code "77") (name "Net-(C5-P$1)") (class "Default")
      (node (ref "C5") (pin "1") (pinfunction "P$1_1") (pintype "passive"))
      (node (ref "R3") (pin "2") (pinfunction "2_2") (pintype "passive"))
      (node (ref "R98") (pin "2") (pinfunction "2_2") (pintype "passive"))
      (node (ref "U11") (pin "9") (pinfunction "IN2+_9") (pintype "bidirectional"))
    )
    (net (code "78") (name "Net-(C5-P$2)") (class "Default")
      (node (ref "C5") (pin "2") (pinfunction "P$2_2") (pintype "passive"))
      (node (ref "R7") (pin "2") (pinfunction "2_2") (pintype "passive"))
      (node (ref "R98") (pin "1") (pinfunction "1_1") (pintype "passive"))
      (node (ref "U11") (pin "10") (pinfunction "IN2-_10") (pintype "bidirectional"))
    )
    (net (code "79") (name "Net-(C6-P$1)") (class "Default")
      (node (ref "C6") (pin "1") (pinfunction "P$1_1") (pintype "passive"))
      (node (ref "U$1") (pin "5") (pinfunction "REF_5") (pintype "bidirectional"))
    )
    (net (code "80") (name "Net-(C7-P$1)") (class "Default")
      (node (ref "C7") (pin "1") (pinfunction "P$1_1") (pintype "passive"))
      (node (ref "U3") (pin "4") (pinfunction "SS_4") (pintype "input"))
    )
    (net (code "81") (name "Net-(C8-P$1)") (class "Default")
      (node (ref "C8") (pin "1") (pinfunction "P$1_1") (pintype "passive"))
      (node (ref "D7") (pin "A") (pinfunction "A_A") (pintype "passive"))
      (node (ref "U4") (pin "2") (pinfunction "OUT_2") (pintype "passive"))
    )
    (net (code "82") (name "Net-(C13-P$1)") (class "Default")
      (node (ref "C13") (pin "1") (pinfunction "P$1_1") (pintype "passive"))
      (node (ref "C18") (pin "2") (pinfunction "P$2_2") (pintype "passive"))
      (node (ref "C19") (pin "1") (pinfunction "P$1_1") (pintype "passive"))
      (node (ref "C25") (pin "1") (pinfunction "P$1_1") (pintype "passive"))
      (node (ref "D4") (pin "C") (pinfunction "C_C") (pintype "passive"))
      (node (ref "D5") (pin "A") (pinfunction "A_A") (pintype "passive"))
      (node (ref "R102") (pin "2") (pinfunction "2_2") (pintype "passive"))
      (node (ref "U$1") (pin "2") (pinfunction "OUT_2") (pintype "bidirectional"))
    )
    (net (code "83") (name "Net-(C14-P$1)") (class "Default")
      (node (ref "C14") (pin "1") (pinfunction "P$1_1") (pintype "passive"))
      (node (ref "D2") (pin "C") (pinfunction "C_C") (pintype "passive"))
      (node (ref "L1") (pin "P$1") (pinfunction "1_P$1") (pintype "passive"))
      (node (ref "U3") (pin "8") (pinfunction "PH_8") (pintype "input"))
    )
    (net (code "84") (name "Net-(C14-P$2)") (class "Default")
      (node (ref "C14") (pin "2") (pinfunction "P$2_2") (pintype "passive"))
      (node (ref "U3") (pin "1") (pinfunction "BOOT_1") (pintype "input"))
    )
    (net (code "85") (name "Net-(C15-P$1)") (class "Default")
      (node (ref "C15") (pin "1") (pinfunction "P$1_1") (pintype "passive"))
      (node (ref "C16") (pin "1") (pinfunction "P$1_1") (pintype "passive"))
      (node (ref "U3") (pin "6") (pinfunction "COMP_6") (pintype "output"))
    )
    (net (code "86") (name "Net-(C15-P$2)") (class "Default")
      (node (ref "C15") (pin "2") (pinfunction "P$2_2") (pintype "passive"))
      (node (ref "R66") (pin "1") (pinfunction "1_1") (pintype "passive"))
    )
    (net (code "87") (name "Net-(C17-P$1)") (class "Default")
      (node (ref "C17") (pin "1") (pinfunction "P$1_1") (pintype "passive"))
      (node (ref "C41") (pin "1") (pinfunction "P$1_1") (pintype "passive"))
      (node (ref "D6") (pin "A") (pinfunction "A_A") (pintype "passive"))
      (node (ref "L1") (pin "P$2") (pinfunction "2_P$2") (pintype "passive"))
      (node (ref "R68") (pin "1") (pinfunction "1_1") (pintype "passive"))
    )
    (net (code "88") (name "Net-(C18-P$1)") (class "Default")
      (node (ref "C18") (pin "1") (pinfunction "P$1_1") (pintype "passive"))
      (node (ref "R102") (pin "1") (pinfunction "1_1") (pintype "passive"))
      (node (ref "R103") (pin "2") (pinfunction "2_2") (pintype "passive"))
      (node (ref "U$1") (pin "3") (pinfunction "FB_3") (pintype "bidirectional"))
    )
    (net (code "89") (name "Net-(C20-P$1)") (class "Default")
      (node (ref "C20") (pin "1") (pinfunction "P$1_1") (pintype "passive"))
      (node (ref "C4") (pin "P$1") (pinfunction "P$1_P$1") (pintype "bidirectional"))
      (node (ref "D7") (pin "C") (pinfunction "C_C") (pintype "passive"))
      (node (ref "L3") (pin "P$1") (pinfunction "1_P$1") (pintype "passive"))
    )
    (net (code "90") (name "Net-(C24-P$1)") (class "Default")
      (node (ref "C24") (pin "1") (pinfunction "P$1_1") (pintype "passive"))
      (node (ref "R54") (pin "1") (pinfunction "1_1") (pintype "passive"))
      (node (ref "U8") (pin "47") (pinfunction "DREF_47") (pintype "bidirectional"))
      (node (ref "U8") (pin "48") (pinfunction "GREF_48") (pintype "bidirectional"))
    )
    (net (code "91") (name "Net-(C34-P$1)") (class "Default")
      (node (ref "C34") (pin "1") (pinfunction "P$1_1") (pintype "passive"))
      (node (ref "R100") (pin "2") (pinfunction "2_2") (pintype "passive"))
      (node (ref "R27") (pin "2") (pinfunction "2_2") (pintype "passive"))
      (node (ref "U5") (pin "9") (pinfunction "IN2+_9") (pintype "bidirectional"))
    )
    (net (code "92") (name "Net-(C34-P$2)") (class "Default")
      (node (ref "C34") (pin "2") (pinfunction "P$2_2") (pintype "passive"))
      (node (ref "R100") (pin "1") (pinfunction "1_1") (pintype "passive"))
      (node (ref "R39") (pin "2") (pinfunction "2_2") (pintype "passive"))
      (node (ref "U5") (pin "10") (pinfunction "IN2-_10") (pintype "bidirectional"))
    )
    (net (code "93") (name "Net-(C35-P$1)") (class "Default")
      (node (ref "C35") (pin "1") (pinfunction "P$1_1") (pintype "passive"))
      (node (ref "R101") (pin "2") (pinfunction "2_2") (pintype "passive"))
      (node (ref "R40") (pin "2") (pinfunction "2_2") (pintype "passive"))
      (node (ref "U5") (pin "16") (pinfunction "IN1+_16") (pintype "bidirectional"))
    )
    (net (code "94") (name "Net-(C35-P$2)") (class "Default")
      (node (ref "C35") (pin "2") (pinfunction "P$2_2") (pintype "passive"))
      (node (ref "R101") (pin "1") (pinfunction "1_1") (pintype "passive"))
      (node (ref "R41") (pin "2") (pinfunction "2_2") (pintype "passive"))
      (node (ref "U5") (pin "15") (pinfunction "IN1-_15") (pintype "bidirectional"))
    )
    (net (code "95") (name "Net-(C51-P$1)") (class "Default")
      (node (ref "C51") (pin "1") (pinfunction "P$1_1") (pintype "passive"))
      (node (ref "R29") (pin "2") (pinfunction "2_2") (pintype "passive"))
      (node (ref "R99") (pin "2") (pinfunction "2_2") (pintype "passive"))
      (node (ref "U11") (pin "16") (pinfunction "IN1+_16") (pintype "bidirectional"))
    )
    (net (code "96") (name "Net-(C51-P$2)") (class "Default")
      (node (ref "C51") (pin "2") (pinfunction "P$2_2") (pintype "passive"))
      (node (ref "R74") (pin "2") (pinfunction "2_2") (pintype "passive"))
      (node (ref "R99") (pin "1") (pinfunction "1_1") (pintype "passive"))
      (node (ref "U11") (pin "15") (pinfunction "IN1-_15") (pintype "bidirectional"))
    )
    (net (code "97") (name "Net-(J3A-D+)") (class "Default")
      (node (ref "CN1") (pin "D+") (pinfunction "D+_D+") (pintype "bidirectional"))
      (node (ref "J3") (pin "76") (pinfunction "D+_76") (pintype "bidirectional"))
    )
    (net (code "98") (name "Net-(J3A-D-)") (class "Default")
      (node (ref "CN1") (pin "D-") (pinfunction "D-_D-") (pintype "bidirectional"))
      (node (ref "J3") (pin "74") (pinfunction "D-_74") (pintype "bidirectional"))
    )
    (net (code "99") (name "Net-(J3A-ID)") (class "Default")
      (node (ref "CN1") (pin "ID") (pinfunction "ID_ID") (pintype "bidirectional"))
      (node (ref "J3") (pin "72") (pinfunction "ID_72") (pintype "bidirectional"))
    )
    (net (code "100") (name "Net-(L3-2)") (class "Default")
      (node (ref "D4") (pin "A") (pinfunction "A_A") (pintype "passive"))
      (node (ref "L3") (pin "P$2") (pinfunction "2_P$2") (pintype "passive"))
      (node (ref "Q4") (pin "3") (pinfunction "D_3") (pintype "bidirectional"))
    )
    (net (code "101") (name "Net-(OK1-A)") (class "Default")
      (node (ref "OK1") (pin "1") (pinfunction "A_1") (pintype "passive"))
      (node (ref "R38") (pin "2") (pinfunction "2_2") (pintype "passive"))
    )
    (net (code "102") (name "Net-(PTC2-2)") (class "Default")
      (node (ref "PTC2") (pin "P$2") (pinfunction "2_P$2") (pintype "passive"))
      (node (ref "U1") (pin "1") (pinfunction "S_2_1") (pintype "passive"))
      (node (ref "U1") (pin "2") (pinfunction "S_2") (pintype "passive"))
      (node (ref "U1") (pin "3") (pinfunction "S_3_3") (pintype "passive"))
    )
    (net (code "103") (name "Net-(Q1-B)") (class "Default")
      (node (ref "Q1") (pin "1") (pinfunction "B_1") (pintype "passive"))
      (node (ref "R10") (pin "1") (pinfunction "1_1") (pintype "passive"))
      (node (ref "R14") (pin "1") (pinfunction "1_1") (pintype "passive"))
    )
    (net (code "104") (name "Net-(Q2-B)") (class "Default")
      (node (ref "Q2") (pin "1") (pinfunction "B_1") (pintype "passive"))
      (node (ref "R11") (pin "1") (pinfunction "1_1") (pintype "passive"))
      (node (ref "R9") (pin "1") (pinfunction "1_1") (pintype "passive"))
    )
    (net (code "105") (name "Net-(Q3-B)") (class "Default")
      (node (ref "Q3") (pin "1") (pinfunction "B_1") (pintype "passive"))
      (node (ref "R17") (pin "1") (pinfunction "1_1") (pintype "passive"))
    )
    (net (code "106") (name "Net-(Q4-G)") (class "Default")
      (node (ref "Q4") (pin "1") (pinfunction "G_1") (pintype "bidirectional"))
      (node (ref "U$1") (pin "1") (pinfunction "EXT_1") (pintype "bidirectional"))
    )
    (net (code "107") (name "Net-(Q4-S)") (class "Default")
      (node (ref "Q4") (pin "2") (pinfunction "S_2") (pintype "bidirectional"))
      (node (ref "R20") (pin "2") (pinfunction "2_2") (pintype "passive"))
      (node (ref "U$1") (pin "8") (pinfunction "CS_8") (pintype "bidirectional"))
    )
    (net (code "108") (name "Net-(Q5-B)") (class "Default")
      (node (ref "Q5") (pin "1") (pinfunction "B_1") (pintype "passive"))
      (node (ref "R47") (pin "1") (pinfunction "1_1") (pintype "passive"))
      (node (ref "R49") (pin "1") (pinfunction "1_1") (pintype "passive"))
    )
    (net (code "109") (name "Net-(Q6-B)") (class "Default")
      (node (ref "Q6") (pin "1") (pinfunction "B_1") (pintype "passive"))
      (node (ref "R46") (pin "1") (pinfunction "1_1") (pintype "passive"))
      (node (ref "R48") (pin "1") (pinfunction "1_1") (pintype "passive"))
    )
    (net (code "110") (name "Net-(Q7-B)") (class "Default")
      (node (ref "Q7") (pin "1") (pinfunction "B_1") (pintype "passive"))
      (node (ref "R51") (pin "1") (pinfunction "1_1") (pintype "passive"))
      (node (ref "R53") (pin "1") (pinfunction "1_1") (pintype "passive"))
    )
    (net (code "111") (name "Net-(Q8-B)") (class "Default")
      (node (ref "Q8") (pin "1") (pinfunction "B_1") (pintype "passive"))
      (node (ref "R50") (pin "1") (pinfunction "1_1") (pintype "passive"))
      (node (ref "R52") (pin "1") (pinfunction "1_1") (pintype "passive"))
    )
    (net (code "112") (name "Net-(SW1-S1)") (class "Default")
      (node (ref "R63") (pin "1") (pinfunction "1_1") (pintype "passive"))
      (node (ref "SW1") (pin "P$3") (pinfunction "S1_P$3") (pintype "passive"))
    )
    (net (code "113") (name "Net-(SW1-S2)") (class "Default")
      (node (ref "R26") (pin "2") (pinfunction "2_2") (pintype "passive"))
      (node (ref "SW1") (pin "P$4") (pinfunction "S2_P$4") (pintype "passive"))
    )
    (net (code "114") (name "Net-(U$36-TX)") (class "Default")
      (node (ref "R21") (pin "2") (pinfunction "2_2") (pintype "passive"))
      (node (ref "U$36") (pin "4") (pinfunction "TX_4") (pintype "bidirectional"))
    )
    (net (code "115") (name "Net-(U3-EN)") (class "Default")
      (node (ref "R1") (pin "2") (pinfunction "2_2") (pintype "passive"))
      (node (ref "R2") (pin "1") (pinfunction "1_1") (pintype "passive"))
      (node (ref "U3") (pin "3") (pinfunction "EN_3") (pintype "input"))
    )
    (net (code "116") (name "Net-(U3-VSENSE)") (class "Default")
      (node (ref "R68") (pin "2") (pinfunction "2_2") (pintype "passive"))
      (node (ref "R69") (pin "1") (pinfunction "1_1") (pintype "passive"))
      (node (ref "U3") (pin "5") (pinfunction "VSENSE_5") (pintype "input"))
    )
    (net (code "117") (name "Net-(U5-DIRN)") (class "Default")
      (node (ref "R44") (pin "1") (pinfunction "1_1") (pintype "passive"))
      (node (ref "U5") (pin "12") (pinfunction "DIRN_12") (pintype "bidirectional"))
    )
    (net (code "118") (name "Net-(U6-VINA+)") (class "Default")
      (node (ref "R24") (pin "2") (pinfunction "2_2") (pintype "passive"))
      (node (ref "R32") (pin "2") (pinfunction "2_2") (pintype "passive"))
      (node (ref "U6") (pin "3") (pinfunction "VINA+_3") (pintype "input"))
    )
    (net (code "119") (name "Net-(U6-VINB+)") (class "Default")
      (node (ref "R25") (pin "2") (pinfunction "2_2") (pintype "passive"))
      (node (ref "R33") (pin "2") (pinfunction "2_2") (pintype "passive"))
      (node (ref "U6") (pin "5") (pinfunction "VINB+_5") (pintype "input"))
    )
    (net (code "120") (name "Net-(U6-VINC+)") (class "Default")
      (node (ref "R30") (pin "2") (pinfunction "2_2") (pintype "passive"))
      (node (ref "R34") (pin "2") (pinfunction "2_2") (pintype "passive"))
      (node (ref "U6") (pin "10") (pinfunction "VINC+_10") (pintype "input"))
    )
    (net (code "121") (name "Net-(U6-VIND+)") (class "Default")
      (node (ref "R31") (pin "2") (pinfunction "2_2") (pintype "passive"))
      (node (ref "R35") (pin "2") (pinfunction "2_2") (pintype "passive"))
      (node (ref "U6") (pin "12") (pinfunction "VIND+_12") (pintype "input"))
    )
    (net (code "122") (name "Net-(U7-P1{slash}TX)") (class "Default")
      (node (ref "R18") (pin "2") (pinfunction "2_2") (pintype "passive"))
      (node (ref "U7") (pin "41") (pinfunction "P1/TX_41") (pintype "bidirectional"))
    )
    (net (code "123") (name "Net-(U11-DIRN)") (class "Default")
      (node (ref "R76") (pin "1") (pinfunction "1_1") (pintype "passive"))
      (node (ref "U11") (pin "12") (pinfunction "DIRN_12") (pintype "bidirectional"))
    )
    (net (code "124") (name "Net-(U12-VINA+)") (class "Default")
      (node (ref "R90") (pin "2") (pinfunction "2_2") (pintype "passive"))
      (node (ref "R92") (pin "2") (pinfunction "2_2") (pintype "passive"))
      (node (ref "U12") (pin "3") (pinfunction "VINA+_3") (pintype "input"))
    )
    (net (code "125") (name "Net-(U12-VINB+)") (class "Default")
      (node (ref "R91") (pin "2") (pinfunction "2_2") (pintype "passive"))
      (node (ref "R93") (pin "2") (pinfunction "2_2") (pintype "passive"))
      (node (ref "U12") (pin "5") (pinfunction "VINB+_5") (pintype "input"))
    )
    (net (code "126") (name "Net-(U13-VINC+)") (class "Default")
      (node (ref "R94") (pin "2") (pinfunction "2_2") (pintype "passive"))
      (node (ref "R96") (pin "2") (pinfunction "2_2") (pintype "passive"))
      (node (ref "U13") (pin "10") (pinfunction "VINC+_10") (pintype "input"))
    )
    (net (code "127") (name "Net-(U13-VIND+)") (class "Default")
      (node (ref "R95") (pin "2") (pinfunction "2_2") (pintype "passive"))
      (node (ref "R97") (pin "2") (pinfunction "2_2") (pintype "passive"))
      (node (ref "U13") (pin "12") (pinfunction "VIND+_12") (pintype "input"))
    )
    (net (code "128") (name "Net-(U14-VINA+)") (class "Default")
      (node (ref "R36") (pin "2") (pinfunction "2_2") (pintype "passive"))
      (node (ref "R86") (pin "2") (pinfunction "2_2") (pintype "passive"))
      (node (ref "U14") (pin "3") (pinfunction "VINA+_3") (pintype "input"))
    )
    (net (code "129") (name "Net-(U14-VINB+)") (class "Default")
      (node (ref "R45") (pin "2") (pinfunction "2_2") (pintype "passive"))
      (node (ref "R87") (pin "2") (pinfunction "2_2") (pintype "passive"))
      (node (ref "U14") (pin "5") (pinfunction "VINB+_5") (pintype "input"))
    )
    (net (code "130") (name "Net-(U14-VINC+)") (class "Default")
      (node (ref "R84") (pin "2") (pinfunction "2_2") (pintype "passive"))
      (node (ref "R88") (pin "2") (pinfunction "2_2") (pintype "passive"))
      (node (ref "U14") (pin "10") (pinfunction "VINC+_10") (pintype "input"))
    )
    (net (code "131") (name "Net-(U14-VIND+)") (class "Default")
      (node (ref "R85") (pin "2") (pinfunction "2_2") (pintype "passive"))
      (node (ref "R89") (pin "2") (pinfunction "2_2") (pintype "passive"))
      (node (ref "U14") (pin "12") (pinfunction "VIND+_12") (pintype "input"))
    )
    (net (code "132") (name "OC1") (class "Default")
      (node (ref "J3") (pin "137") (pinfunction "PE4_137") (pintype "bidirectional"))
      (node (ref "R46") (pin "2") (pinfunction "2_2") (pintype "passive"))
    )
    (net (code "133") (name "OC2") (class "Default")
      (node (ref "J3") (pin "139") (pinfunction "PE5_139") (pintype "bidirectional"))
      (node (ref "R47") (pin "2") (pinfunction "2_2") (pintype "passive"))
    )
    (net (code "134") (name "ODC1") (class "Default")
      (node (ref "J3") (pin "135") (pinfunction "PE3_135") (pintype "bidirectional"))
      (node (ref "R14") (pin "2") (pinfunction "2_2") (pintype "passive"))
    )
    (net (code "135") (name "ODC2") (class "Default")
      (node (ref "J3") (pin "141") (pinfunction "PE6_141") (pintype "bidirectional"))
      (node (ref "R50") (pin "2") (pinfunction "2_2") (pintype "passive"))
    )
    (net (code "136") (name "ODC3") (class "Default")
      (node (ref "J3") (pin "133") (pinfunction "PE2_133") (pintype "bidirectional"))
      (node (ref "R11") (pin "2") (pinfunction "2_2") (pintype "passive"))
    )
    (net (code "137") (name "ODC4") (class "Default")
      (node (ref "J3") (pin "143") (pinfunction "PC13_143") (pintype "bidirectional"))
      (node (ref "R51") (pin "2") (pinfunction "2_2") (pintype "passive"))
    )
    (net (code "138") (name "ODI1") (class "Default")
      (node (ref "D3") (pin "C") (pinfunction "C_C") (pintype "passive"))
      (node (ref "J1") (pin "L2") (pinfunction "L_L2") (pintype "bidirectional"))
      (node (ref "Q1") (pin "3") (pinfunction "C_3") (pintype "passive"))
    )
    (net (code "139") (name "ODI2") (class "Default")
      (node (ref "D10") (pin "C") (pinfunction "C_C") (pintype "passive"))
      (node (ref "J1") (pin "M2") (pinfunction "M_M2") (pintype "bidirectional"))
      (node (ref "Q8") (pin "3") (pinfunction "C_3") (pintype "passive"))
    )
    (net (code "140") (name "ODI3") (class "Default")
      (node (ref "D1") (pin "C") (pinfunction "C_C") (pintype "passive"))
      (node (ref "J1") (pin "L3") (pinfunction "L_L3") (pintype "bidirectional"))
      (node (ref "Q2") (pin "3") (pinfunction "C_3") (pintype "passive"))
    )
    (net (code "141") (name "ODI4") (class "Default")
      (node (ref "D11") (pin "C") (pinfunction "C_C") (pintype "passive"))
      (node (ref "J1") (pin "M3") (pinfunction "M_M3") (pintype "bidirectional"))
      (node (ref "Q7") (pin "3") (pinfunction "C_3") (pintype "passive"))
    )
    (net (code "142") (name "OILP") (class "Default")
      (node (ref "J1") (pin "C1") (pinfunction "C_C1") (pintype "bidirectional"))
      (node (ref "R78") (pin "2") (pinfunction "2_2") (pintype "passive"))
      (node (ref "U8") (pin "29") (pinfunction "D18_29") (pintype "bidirectional"))
    )
    (net (code "143") (name "OILPI") (class "Default")
      (node (ref "J3") (pin "49") (pinfunction "PD8_49") (pintype "bidirectional"))
      (node (ref "U8") (pin "20") (pinfunction "S18_20") (pintype "bidirectional"))
    )
    (net (code "144") (name "PWR_OUT") (class "Default")
      (node (ref "J3") (pin "99") (pinfunction "PD3_99") (pintype "bidirectional"))
      (node (ref "OK1") (pin "5") (pinfunction "COL_5") (pintype "passive"))
      (node (ref "R83") (pin "2") (pinfunction "2_2") (pintype "passive"))
    )
    (net (code "145") (name "RESET") (class "Default")
      (node (ref "J3") (pin "90") (pinfunction "RESET_90") (pintype "bidirectional"))
      (node (ref "JTAG1") (pin "15") (pinfunction "15_15") (pintype "passive"))
    )
    (net (code "146") (name "RLY1") (class "Default")
      (node (ref "D8") (pin "C") (pinfunction "C_C") (pintype "passive"))
      (node (ref "J1") (pin "L1") (pinfunction "L_L1") (pintype "bidirectional"))
      (node (ref "Q6") (pin "3") (pinfunction "C_3") (pintype "passive"))
    )
    (net (code "147") (name "RLY2") (class "Default")
      (node (ref "D9") (pin "C") (pinfunction "C_C") (pintype "passive"))
      (node (ref "J1") (pin "M1") (pinfunction "M_M1") (pintype "bidirectional"))
      (node (ref "Q5") (pin "3") (pinfunction "C_3") (pintype "passive"))
    )
    (net (code "148") (name "RPM1") (class "Default")
      (node (ref "J3") (pin "23") (pinfunction "PE9_23") (pintype "bidirectional"))
      (node (ref "R42") (pin "1") (pinfunction "1_1") (pintype "passive"))
      (node (ref "TP1") (pin "TESTPOINT") (pinfunction "TESTPOINT_TESTPOINT") (pintype "bidirectional"))
      (node (ref "U5") (pin "4") (pinfunction "COUT1_4") (pintype "bidirectional"))
    )
    (net (code "149") (name "RPM1GIN") (class "Default")
      (node (ref "J2") (pin "B4") (pinfunction "B_B4") (pintype "bidirectional"))
      (node (ref "R39") (pin "1") (pinfunction "1_1") (pintype "passive"))
    )
    (net (code "150") (name "RPM1IN") (class "Default")
      (node (ref "J2") (pin "A4") (pinfunction "A_A4") (pintype "bidirectional"))
      (node (ref "R27") (pin "1") (pinfunction "1_1") (pintype "passive"))
    )
    (net (code "151") (name "RPM2") (class "Default")
      (node (ref "J3") (pin "19") (pinfunction "PE7_19") (pintype "bidirectional"))
      (node (ref "R43") (pin "1") (pinfunction "1_1") (pintype "passive"))
      (node (ref "TP2") (pin "TESTPOINT") (pinfunction "TESTPOINT_TESTPOINT") (pintype "bidirectional"))
      (node (ref "U5") (pin "5") (pinfunction "COUT2_5") (pintype "bidirectional"))
    )
    (net (code "152") (name "RPM2GIN") (class "Default")
      (node (ref "J2") (pin "B3") (pinfunction "B_B3") (pintype "bidirectional"))
      (node (ref "R41") (pin "1") (pinfunction "1_1") (pintype "passive"))
    )
    (net (code "153") (name "RPM2IN") (class "Default")
      (node (ref "J2") (pin "A3") (pinfunction "A_A3") (pintype "bidirectional"))
      (node (ref "R40") (pin "1") (pinfunction "1_1") (pintype "passive"))
    )
    (net (code "154") (name "RPM3") (class "Default")
      (node (ref "J3") (pin "27") (pinfunction "PE11_27") (pintype "bidirectional"))
      (node (ref "R28") (pin "1") (pinfunction "1_1") (pintype "passive"))
      (node (ref "TP3") (pin "TESTPOINT") (pinfunction "TESTPOINT_TESTPOINT") (pintype "bidirectional"))
      (node (ref "U11") (pin "4") (pinfunction "COUT1_4") (pintype "bidirectional"))
    )
    (net (code "155") (name "RPM3GIN") (class "Default")
      (node (ref "J2") (pin "B2") (pinfunction "B_B2") (pintype "bidirectional"))
      (node (ref "R7") (pin "1") (pinfunction "1_1") (pintype "passive"))
    )
    (net (code "156") (name "RPM3IN") (class "Default")
      (node (ref "J2") (pin "A2") (pinfunction "A_A2") (pintype "bidirectional"))
      (node (ref "R3") (pin "1") (pinfunction "1_1") (pintype "passive"))
    )
    (net (code "157") (name "RPM4") (class "Default")
      (node (ref "J3") (pin "25") (pinfunction "PE10_25") (pintype "bidirectional"))
      (node (ref "R75") (pin "1") (pinfunction "1_1") (pintype "passive"))
      (node (ref "TP4") (pin "TESTPOINT") (pinfunction "TESTPOINT_TESTPOINT") (pintype "bidirectional"))
      (node (ref "U11") (pin "5") (pinfunction "COUT2_5") (pintype "bidirectional"))
    )
    (net (code "158") (name "RPM4GIN") (class "Default")
      (node (ref "J2") (pin "B1") (pinfunction "B_B1") (pintype "bidirectional"))
      (node (ref "R74") (pin "1") (pinfunction "1_1") (pintype "passive"))
    )
    (net (code "159") (name "RPM4IN") (class "Default")
      (node (ref "J2") (pin "A1") (pinfunction "A_A1") (pintype "bidirectional"))
      (node (ref "R29") (pin "1") (pinfunction "1_1") (pintype "passive"))
    )
    (net (code "160") (name "RTS") (class "Default")
      (node (ref "J3") (pin "29") (pinfunction "PE12_29") (pintype "bidirectional"))
      (node (ref "U7") (pin "24") (pinfunction "P3_24") (pintype "bidirectional"))
      (node (ref "XB1") (pin "16") (pinfunction "~{RTS}/AD6/DIO6_16") (pintype "bidirectional"))
    )
    (net (code "161") (name "SCK") (class "Default")
      (node (ref "J3") (pin "43") (pinfunction "PB13_43") (pintype "bidirectional"))
      (node (ref "U7") (pin "34") (pinfunction "CLK_34") (pintype "bidirectional"))
      (node (ref "U9") (pin "13") (pinfunction "SCL_13") (pintype "bidirectional"))
      (node (ref "X1") (pin "13") (pinfunction "S_13") (pintype "passive"))
    )
    (net (code "162") (name "SCL") (class "Default")
      (node (ref "X1") (pin "10") (pinfunction "S_10") (pintype "passive"))
    )
    (net (code "163") (name "SDA") (class "Default")
      (node (ref "X1") (pin "9") (pinfunction "S_9") (pintype "passive"))
    )
    (net (code "164") (name "SDIO_CMD") (class "Default")
      (node (ref "J3") (pin "97") (pinfunction "PD2_97") (pintype "bidirectional"))
      (node (ref "R4") (pin "2") (pinfunction "2_2") (pintype "passive"))
      (node (ref "U$2") (pin "3") (pinfunction "DATA_IN_3") (pintype "input"))
    )
    (net (code "165") (name "SDIO_D0") (class "Default")
      (node (ref "J3") (pin "69") (pinfunction "PC8_69") (pintype "bidirectional"))
      (node (ref "R22") (pin "2") (pinfunction "2_2") (pintype "passive"))
      (node (ref "U$2") (pin "7") (pinfunction "DATA_OUT_7") (pintype "output"))
    )
    (net (code "166") (name "SDIO_D1") (class "Default")
      (node (ref "J3") (pin "71") (pinfunction "PC9_71") (pintype "bidirectional"))
      (node (ref "R6") (pin "2") (pinfunction "2_2") (pintype "passive"))
      (node (ref "U$2") (pin "8") (pinfunction "DAT1_8") (pintype "bidirectional"))
    )
    (net (code "167") (name "SDIO_D2") (class "Default")
      (node (ref "J3") (pin "87") (pinfunction "PC10_87") (pintype "bidirectional"))
      (node (ref "R8") (pin "2") (pinfunction "2_2") (pintype "passive"))
      (node (ref "U$2") (pin "1") (pinfunction "DAT2_1") (pintype "bidirectional"))
    )
    (net (code "168") (name "SDIO_D3") (class "Default")
      (node (ref "J3") (pin "89") (pinfunction "PC11_89") (pintype "bidirectional"))
      (node (ref "R5") (pin "2") (pinfunction "2_2") (pintype "passive"))
      (node (ref "U$2") (pin "2") (pinfunction "CS_2") (pintype "input"))
    )
    (net (code "169") (name "SDIO_SCK") (class "Default")
      (node (ref "J3") (pin "91") (pinfunction "PC12_91") (pintype "bidirectional"))
      (node (ref "U$2") (pin "5") (pinfunction "SCLK_5") (pintype "input"))
    )
    (net (code "170") (name "SD_IN") (class "Default")
      (node (ref "J3") (pin "73") (pinfunction "PA8_73") (pintype "bidirectional"))
      (node (ref "U$2") (pin "CD1") (pinfunction "CARD_DETECT_CD1") (pintype "passive"))
    )
    (net (code "171") (name "SPEED") (class "Default")
      (node (ref "J2") (pin "J3") (pinfunction "J_J3") (pintype "bidirectional"))
      (node (ref "R90") (pin "1") (pinfunction "1_1") (pintype "passive"))
    )
    (net (code "172") (name "SPEEDB") (class "Default")
      (node (ref "J3") (pin "15") (pinfunction "PB0/AN8_15") (pintype "bidirectional"))
      (node (ref "U12") (pin "1") (pinfunction "VOUTA_1") (pintype "output"))
      (node (ref "U12") (pin "2") (pinfunction "VINA-_2") (pintype "input"))
    )
    (net (code "173") (name "STEERING-ANGLE") (class "Default")
      (node (ref "J1") (pin "H3") (pinfunction "H_H3") (pintype "bidirectional"))
      (node (ref "R36") (pin "1") (pinfunction "1_1") (pintype "passive"))
    )
    (net (code "174") (name "STEERING-ANGLEB") (class "Default")
      (node (ref "J3") (pin "3") (pinfunction "PA4/AN4_3") (pintype "bidirectional"))
      (node (ref "U14") (pin "1") (pinfunction "VOUTA_1") (pintype "output"))
      (node (ref "U14") (pin "2") (pinfunction "VINA-_2") (pintype "input"))
    )
    (net (code "175") (name "TELE_RX") (class "Default")
      (node (ref "J3") (pin "105") (pinfunction "PD6_105") (pintype "bidirectional"))
      (node (ref "R16") (pin "1") (pinfunction "1_1") (pintype "passive"))
      (node (ref "R18") (pin "1") (pinfunction "1_1") (pintype "passive"))
      (node (ref "XB1") (pin "2") (pinfunction "DOUT_2") (pintype "output"))
    )
    (net (code "176") (name "TELE_TX") (class "Default")
      (node (ref "J3") (pin "103") (pinfunction "PD5_103") (pintype "bidirectional"))
      (node (ref "U7") (pin "40") (pinfunction "P0/RX_40") (pintype "bidirectional"))
      (node (ref "XB1") (pin "3") (pinfunction "DIN/~{CONFIG}_3") (pintype "input"))
    )
    (net (code "177") (name "TRAVEL1") (class "Default")
      (node (ref "J2") (pin "L3") (pinfunction "L_L3") (pintype "bidirectional"))
      (node (ref "R25") (pin "1") (pinfunction "1_1") (pintype "passive"))
    )
    (net (code "178") (name "TRAVEL1B") (class "Default")
      (node (ref "J3") (pin "151") (pinfunction "PC3/AN13_151") (pintype "bidirectional"))
      (node (ref "U6") (pin "6") (pinfunction "VINB-_6") (pintype "input"))
      (node (ref "U6") (pin "7") (pinfunction "VOUTB_7") (pintype "output"))
    )
    (net (code "179") (name "TRAVEL2") (class "Default")
      (node (ref "J2") (pin "L4") (pinfunction "L_L4") (pintype "bidirectional"))
      (node (ref "R24") (pin "1") (pinfunction "1_1") (pintype "passive"))
    )
    (net (code "180") (name "TRAVEL2B") (class "Default")
      (node (ref "J3") (pin "149") (pinfunction "PC2/AN12_149") (pintype "bidirectional"))
      (node (ref "U6") (pin "1") (pinfunction "VOUTA_1") (pintype "output"))
      (node (ref "U6") (pin "2") (pinfunction "VINA-_2") (pintype "input"))
    )
    (net (code "181") (name "TRAVEL3") (class "Default")
      (node (ref "J2") (pin "L2") (pinfunction "L_L2") (pintype "bidirectional"))
      (node (ref "R30") (pin "1") (pinfunction "1_1") (pintype "passive"))
    )
    (net (code "182") (name "TRAVEL3B") (class "Default")
      (node (ref "J3") (pin "145") (pinfunction "PC0/AN10_145") (pintype "bidirectional"))
      (node (ref "U6") (pin "8") (pinfunction "VOUTC_8") (pintype "output"))
      (node (ref "U6") (pin "9") (pinfunction "VINC-_9") (pintype "input"))
    )
    (net (code "183") (name "TRAVEL4") (class "Default")
      (node (ref "J2") (pin "L1") (pinfunction "L_L1") (pintype "bidirectional"))
      (node (ref "R31") (pin "1") (pinfunction "1_1") (pintype "passive"))
    )
    (net (code "184") (name "TRAVEL4B") (class "Default")
      (node (ref "J3") (pin "147") (pinfunction "PC1/AN11_147") (pintype "bidirectional"))
      (node (ref "U6") (pin "13") (pinfunction "VIND-_13") (pintype "input"))
      (node (ref "U6") (pin "14") (pinfunction "VOUTD_14") (pintype "output"))
    )
    (net (code "185") (name "UPS_EN") (class "Default")
      (node (ref "J3") (pin "33") (pinfunction "PE14_33") (pintype "bidirectional"))
      (node (ref "U$1") (pin "4") (pinfunction "SHDN_4") (pintype "bidirectional"))
    )
    (net (code "186") (name "VBUS") (class "Default")
      (node (ref "CN1") (pin "VBUS") (pinfunction "VBUS_VBUS") (pintype "power_in"))
    )
    (net (code "187") (name "VCC") (class "Default")
      (node (ref "J1") (pin "L4") (pinfunction "L_L4") (pintype "bidirectional"))
      (node (ref "U1") (pin "5") (pinfunction "D_4_5") (pintype "passive"))
      (node (ref "U1") (pin "6") (pinfunction "D_6") (pintype "passive"))
      (node (ref "U1") (pin "7") (pinfunction "D_2_7") (pintype "passive"))
      (node (ref "U1") (pin "8") (pinfunction "D_3_8") (pintype "passive"))
      (node (ref "X1") (pin "3") (pinfunction "S_3") (pintype "passive"))
    )
    (net (code "188") (name "VTEMP") (class "Default")
      (node (ref "J2") (pin "F1") (pinfunction "F_F1") (pintype "bidirectional"))
      (node (ref "R13") (pin "2") (pinfunction "2_2") (pintype "passive"))
      (node (ref "U13") (pin "5") (pinfunction "VINB+_5") (pintype "input"))
    )
    (net (code "189") (name "VTEMP2") (class "Default")
      (node (ref "J2") (pin "F3") (pinfunction "F_F3") (pintype "bidirectional"))
      (node (ref "R12") (pin "2") (pinfunction "2_2") (pintype "passive"))
      (node (ref "U12") (pin "10") (pinfunction "VINC+_10") (pintype "input"))
    )
    (net (code "190") (name "VTEMP2B") (class "Default")
      (node (ref "J3") (pin "11") (pinfunction "PC4/AN15_11") (pintype "bidirectional"))
      (node (ref "U12") (pin "8") (pinfunction "VOUTC_8") (pintype "output"))
      (node (ref "U12") (pin "9") (pinfunction "VINC-_9") (pintype "input"))
    )
    (net (code "191") (name "VTEMPB") (class "Default")
      (node (ref "J3") (pin "9") (pinfunction "PA7/AN7_9") (pintype "bidirectional"))
      (node (ref "U13") (pin "6") (pinfunction "VINB-_6") (pintype "input"))
      (node (ref "U13") (pin "7") (pinfunction "VOUTB_7") (pintype "output"))
    )
    (net (code "192") (name "YAW") (class "Default")
      (node (ref "J1") (pin "A3") (pinfunction "A_A3") (pintype "bidirectional"))
      (node (ref "R84") (pin "1") (pinfunction "1_1") (pintype "passive"))
    )
    (net (code "193") (name "YAWB") (class "Default")
      (node (ref "J3") (pin "155") (pinfunction "PA1/AN1_155") (pintype "bidirectional"))
      (node (ref "U14") (pin "8") (pinfunction "VOUTC_8") (pintype "output"))
      (node (ref "U14") (pin "9") (pinfunction "VINC-_9") (pintype "input"))
    )
    (net (code "194") (name "unconnected-(J1B-G-PadG2)") (class "Default")
      (node (ref "J1") (pin "G2") (pinfunction "G_G2") (pintype "bidirectional"))
    )
    (net (code "195") (name "unconnected-(J1B-H-PadH2)") (class "Default")
      (node (ref "J1") (pin "H2") (pinfunction "H_H2") (pintype "bidirectional"))
    )
    (net (code "196") (name "unconnected-(J2D-C-PadC4)") (class "Default")
      (node (ref "J2") (pin "C4") (pinfunction "C_C4") (pintype "bidirectional"))
    )
    (net (code "197") (name "unconnected-(J2D-D-PadD4)") (class "Default")
      (node (ref "J2") (pin "D4") (pinfunction "D_D4") (pintype "bidirectional"))
    )
    (net (code "198") (name "unconnected-(J4-CTS-PadP$5)") (class "Default")
      (node (ref "J4") (pin "P$5") (pinfunction "CTS_P$5") (pintype "bidirectional"))
    )
    (net (code "199") (name "unconnected-(J4-DTR-PadP$1)") (class "Default")
      (node (ref "J4") (pin "P$1") (pinfunction "DTR_P$1") (pintype "bidirectional"))
    )
    (net (code "200") (name "unconnected-(J4-VCC-PadP$4)") (class "Default")
      (node (ref "J4") (pin "P$4") (pinfunction "VCC_P$4") (pintype "bidirectional"))
    )
    (net (code "201") (name "unconnected-(JTAG1-Pad11)") (class "Default")
      (node (ref "JTAG1") (pin "11") (pinfunction "11_11") (pintype "passive"))
    )
    (net (code "202") (name "unconnected-(JTAG1-Pad17)") (class "Default")
      (node (ref "JTAG1") (pin "17") (pinfunction "17_17") (pintype "passive"))
    )
    (net (code "203") (name "unconnected-(JTAG1-Pad19)") (class "Default")
      (node (ref "JTAG1") (pin "19") (pinfunction "19_19") (pintype "passive"))
    )
    (net (code "204") (name "unconnected-(OK1-B-Pad6)") (class "Default")
      (node (ref "OK1") (pin "6") (pinfunction "B_6") (pintype "passive"))
    )
    (net (code "205") (name "unconnected-(SW1-O1-PadP$1)") (class "Default")
      (node (ref "SW1") (pin "P$1") (pinfunction "O1_P$1") (pintype "passive"))
    )
    (net (code "206") (name "unconnected-(SW1-O2-PadP$6)") (class "Default")
      (node (ref "SW1") (pin "P$6") (pinfunction "O2_P$6") (pintype "passive"))
    )
    (net (code "207") (name "unconnected-(U$2-CARD_DETECT1-PadCD2)") (class "Default")
      (node (ref "U$2") (pin "CD2") (pinfunction "CARD_DETECT1_CD2") (pintype "passive"))
    )
    (net (code "208") (name "unconnected-(U$36-NC-Pad6)") (class "Default")
      (node (ref "U$36") (pin "6") (pinfunction "NC_6") (pintype "bidirectional"))
    )
    (net (code "209") (name "unconnected-(U5-EXT1-Pad2)") (class "Default")
      (node (ref "U5") (pin "2") (pinfunction "EXT1_2") (pintype "bidirectional"))
    )
    (net (code "210") (name "unconnected-(U5-EXT2-Pad7)") (class "Default")
      (node (ref "U5") (pin "7") (pinfunction "EXT2_7") (pintype "bidirectional"))
    )
    (net (code "211") (name "unconnected-(U7-P4-Pad21)") (class "Default")
      (node (ref "U7") (pin "21") (pinfunction "P4_21") (pintype "bidirectional"))
    )
    (net (code "212") (name "unconnected-(U7-P8-Pad22)") (class "Default")
      (node (ref "U7") (pin "22") (pinfunction "P8_22") (pintype "bidirectional"))
    )
    (net (code "213") (name "unconnected-(U7-P9-Pad18)") (class "Default")
      (node (ref "U7") (pin "18") (pinfunction "P9_18") (pintype "bidirectional"))
    )
    (net (code "214") (name "unconnected-(U7-P10-Pad20)") (class "Default")
      (node (ref "U7") (pin "20") (pinfunction "P10_20") (pintype "bidirectional"))
    )
    (net (code "215") (name "unconnected-(U7-P11-Pad39)") (class "Default")
      (node (ref "U7") (pin "39") (pinfunction "P11_39") (pintype "bidirectional"))
    )
    (net (code "216") (name "unconnected-(U7-P12-Pad42)") (class "Default")
      (node (ref "U7") (pin "42") (pinfunction "P12_42") (pintype "bidirectional"))
    )
    (net (code "217") (name "unconnected-(U7-P13-Pad5)") (class "Default")
      (node (ref "U7") (pin "5") (pinfunction "P13_5") (pintype "bidirectional"))
    )
    (net (code "218") (name "unconnected-(U7-P14-Pad6)") (class "Default")
      (node (ref "U7") (pin "6") (pinfunction "P14_6") (pintype "bidirectional"))
    )
    (net (code "219") (name "unconnected-(U7-P15-Pad7)") (class "Default")
      (node (ref "U7") (pin "7") (pinfunction "P15_7") (pintype "bidirectional"))
    )
    (net (code "220") (name "unconnected-(U7-P16-Pad8)") (class "Default")
      (node (ref "U7") (pin "8") (pinfunction "P16_8") (pintype "bidirectional"))
    )
    (net (code "221") (name "unconnected-(U7-P17-Pad11)") (class "Default")
      (node (ref "U7") (pin "11") (pinfunction "P17_11") (pintype "bidirectional"))
    )
    (net (code "222") (name "unconnected-(U7-P18-Pad10)") (class "Default")
      (node (ref "U7") (pin "10") (pinfunction "P18_10") (pintype "bidirectional"))
    )
    (net (code "223") (name "unconnected-(U7-P19-Pad12)") (class "Default")
      (node (ref "U7") (pin "12") (pinfunction "P19_12") (pintype "bidirectional"))
    )
    (net (code "224") (name "unconnected-(U7-P20-Pad13)") (class "Default")
      (node (ref "U7") (pin "13") (pinfunction "P20_13") (pintype "bidirectional"))
    )
    (net (code "225") (name "unconnected-(U7-P21-Pad15)") (class "Default")
      (node (ref "U7") (pin "15") (pinfunction "P21_15") (pintype "bidirectional"))
    )
    (net (code "226") (name "unconnected-(U7-P22-Pad14)") (class "Default")
      (node (ref "U7") (pin "14") (pinfunction "P22_14") (pintype "bidirectional"))
    )
    (net (code "227") (name "unconnected-(U7-P23-Pad17)") (class "Default")
      (node (ref "U7") (pin "17") (pinfunction "P23_17") (pintype "bidirectional"))
    )
    (net (code "228") (name "unconnected-(U7-Pad3,3V)") (class "Default")
      (node (ref "U7") (pin "3,3V") (pinfunction "3,3V_3,3V") (pintype "bidirectional"))
    )
    (net (code "229") (name "unconnected-(U7-RST-Pad9)") (class "Default")
      (node (ref "U7") (pin "9") (pinfunction "RST_9") (pintype "bidirectional"))
    )
    (net (code "230") (name "unconnected-(U8-D9-Pad38)") (class "Default")
      (node (ref "U8") (pin "38") (pinfunction "D9_38") (pintype "bidirectional"))
    )
    (net (code "231") (name "unconnected-(U8-D19-Pad28)") (class "Default")
      (node (ref "U8") (pin "28") (pinfunction "D19_28") (pintype "bidirectional"))
    )
    (net (code "232") (name "unconnected-(U8-S9-Pad11)") (class "Default")
      (node (ref "U8") (pin "11") (pinfunction "S9_11") (pintype "bidirectional"))
    )
    (net (code "233") (name "unconnected-(U8-S19-Pad21)") (class "Default")
      (node (ref "U8") (pin "21") (pinfunction "S19_21") (pintype "bidirectional"))
    )
    (net (code "234") (name "unconnected-(U9-INT1-Pad4)") (class "Default")
      (node (ref "U9") (pin "4") (pinfunction "INT1_4") (pintype "bidirectional"))
    )
    (net (code "235") (name "unconnected-(U9-INT2-Pad9)") (class "Default")
      (node (ref "U9") (pin "9") (pinfunction "INT2_9") (pintype "bidirectional"))
    )
    (net (code "236") (name "unconnected-(U9-NC-Pad11)") (class "Default")
      (node (ref "U9") (pin "11") (pinfunction "NC_11") (pintype "bidirectional"))
    )
    (net (code "237") (name "unconnected-(U9-OCS-Pad10)") (class "Default")
      (node (ref "U9") (pin "10") (pinfunction "OCS_10") (pintype "bidirectional"))
    )
    (net (code "238") (name "unconnected-(U10-NC-Pad8)") (class "Default")
      (node (ref "U10") (pin "8") (pinfunction "NC_8") (pintype "no_connect"))
    )
    (net (code "239") (name "unconnected-(U10-NC_2-Pad5)") (class "Default")
      (node (ref "U10") (pin "5") (pinfunction "NC_2_5") (pintype "no_connect"))
    )
    (net (code "240") (name "unconnected-(U11-EXT1-Pad2)") (class "Default")
      (node (ref "U11") (pin "2") (pinfunction "EXT1_2") (pintype "bidirectional"))
    )
    (net (code "241") (name "unconnected-(U11-EXT2-Pad7)") (class "Default")
      (node (ref "U11") (pin "7") (pinfunction "EXT2_7") (pintype "bidirectional"))
    )
    (net (code "242") (name "unconnected-(XB1-AD0{slash}DIO0-Pad20)") (class "Default")
      (node (ref "XB1") (pin "20") (pinfunction "AD0/DIO0_20") (pintype "bidirectional"))
    )
    (net (code "243") (name "unconnected-(XB1-AD1{slash}DIO1-Pad19)") (class "Default")
      (node (ref "XB1") (pin "19") (pinfunction "AD1/DIO1_19") (pintype "bidirectional"))
    )
    (net (code "244") (name "unconnected-(XB1-AD2{slash}DIO2-Pad18)") (class "Default")
      (node (ref "XB1") (pin "18") (pinfunction "AD2/DIO2_18") (pintype "bidirectional"))
    )
    (net (code "245") (name "unconnected-(XB1-ASSOC{slash}AD5{slash}DIO5-Pad15)") (class "Default")
      (node (ref "XB1") (pin "15") (pinfunction "ASSOC/AD5/DIO5_15") (pintype "bidirectional"))
    )
    (net (code "246") (name "unconnected-(XB1-CD{slash}DOUT_EN{slash}DO8-Pad4)") (class "Default")
      (node (ref "XB1") (pin "4") (pinfunction "CD/DOUT_EN/DO8_4") (pintype "output"))
    )
    (net (code "247") (name "unconnected-(XB1-COORD_SEL{slash}AD3{slash}DIO3-Pad17)") (class "Default")
      (node (ref "XB1") (pin "17") (pinfunction "COORD_SEL/AD3/DIO3_17") (pintype "bidirectional"))
    )
    (net (code "248") (name "unconnected-(XB1-ON{slash}~{SLEEP}-Pad13)") (class "Default")
      (node (ref "XB1") (pin "13") (pinfunction "ON/~{SLEEP}_13") (pintype "output"))
    )
    (net (code "249") (name "unconnected-(XB1-PWM0{slash}RSSI-Pad6)") (class "Default")
      (node (ref "XB1") (pin "6") (pinfunction "PWM0/RSSI_6") (pintype "output"))
    )
    (net (code "250") (name "unconnected-(XB1-RF_TX{slash}AD4{slash}DIO4-Pad11)") (class "Default")
      (node (ref "XB1") (pin "11") (pinfunction "RF_TX/AD4/DIO4_11") (pintype "bidirectional"))
    )
    (net (code "251") (name "unconnected-(XB1-VREF-Pad14)") (class "Default")
      (node (ref "XB1") (pin "14") (pinfunction "VREF_14") (pintype "input"))
    )
    (net (code "252") (name "unconnected-(XB1-~{DTR}{slash}SLEEP_RQ{slash}DI8-Pad9)") (class "Default")
      (node (ref "XB1") (pin "9") (pinfunction "~{DTR}/SLEEP_RQ/DI8_9") (pintype "bidirectional"))
    )
  )
)
